# POVRotor.net
KiCad netlist of a schematic drawn in EAGLE
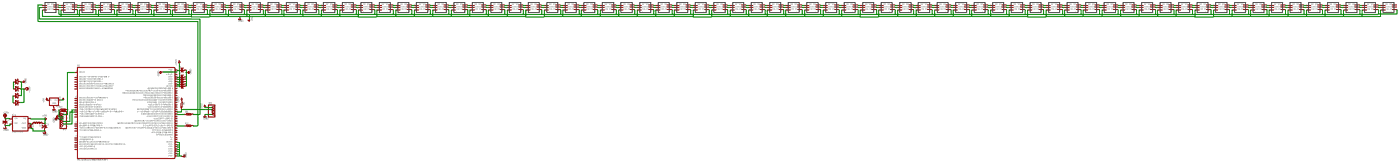
[diagram p0: schematic, sheet 1, overview]
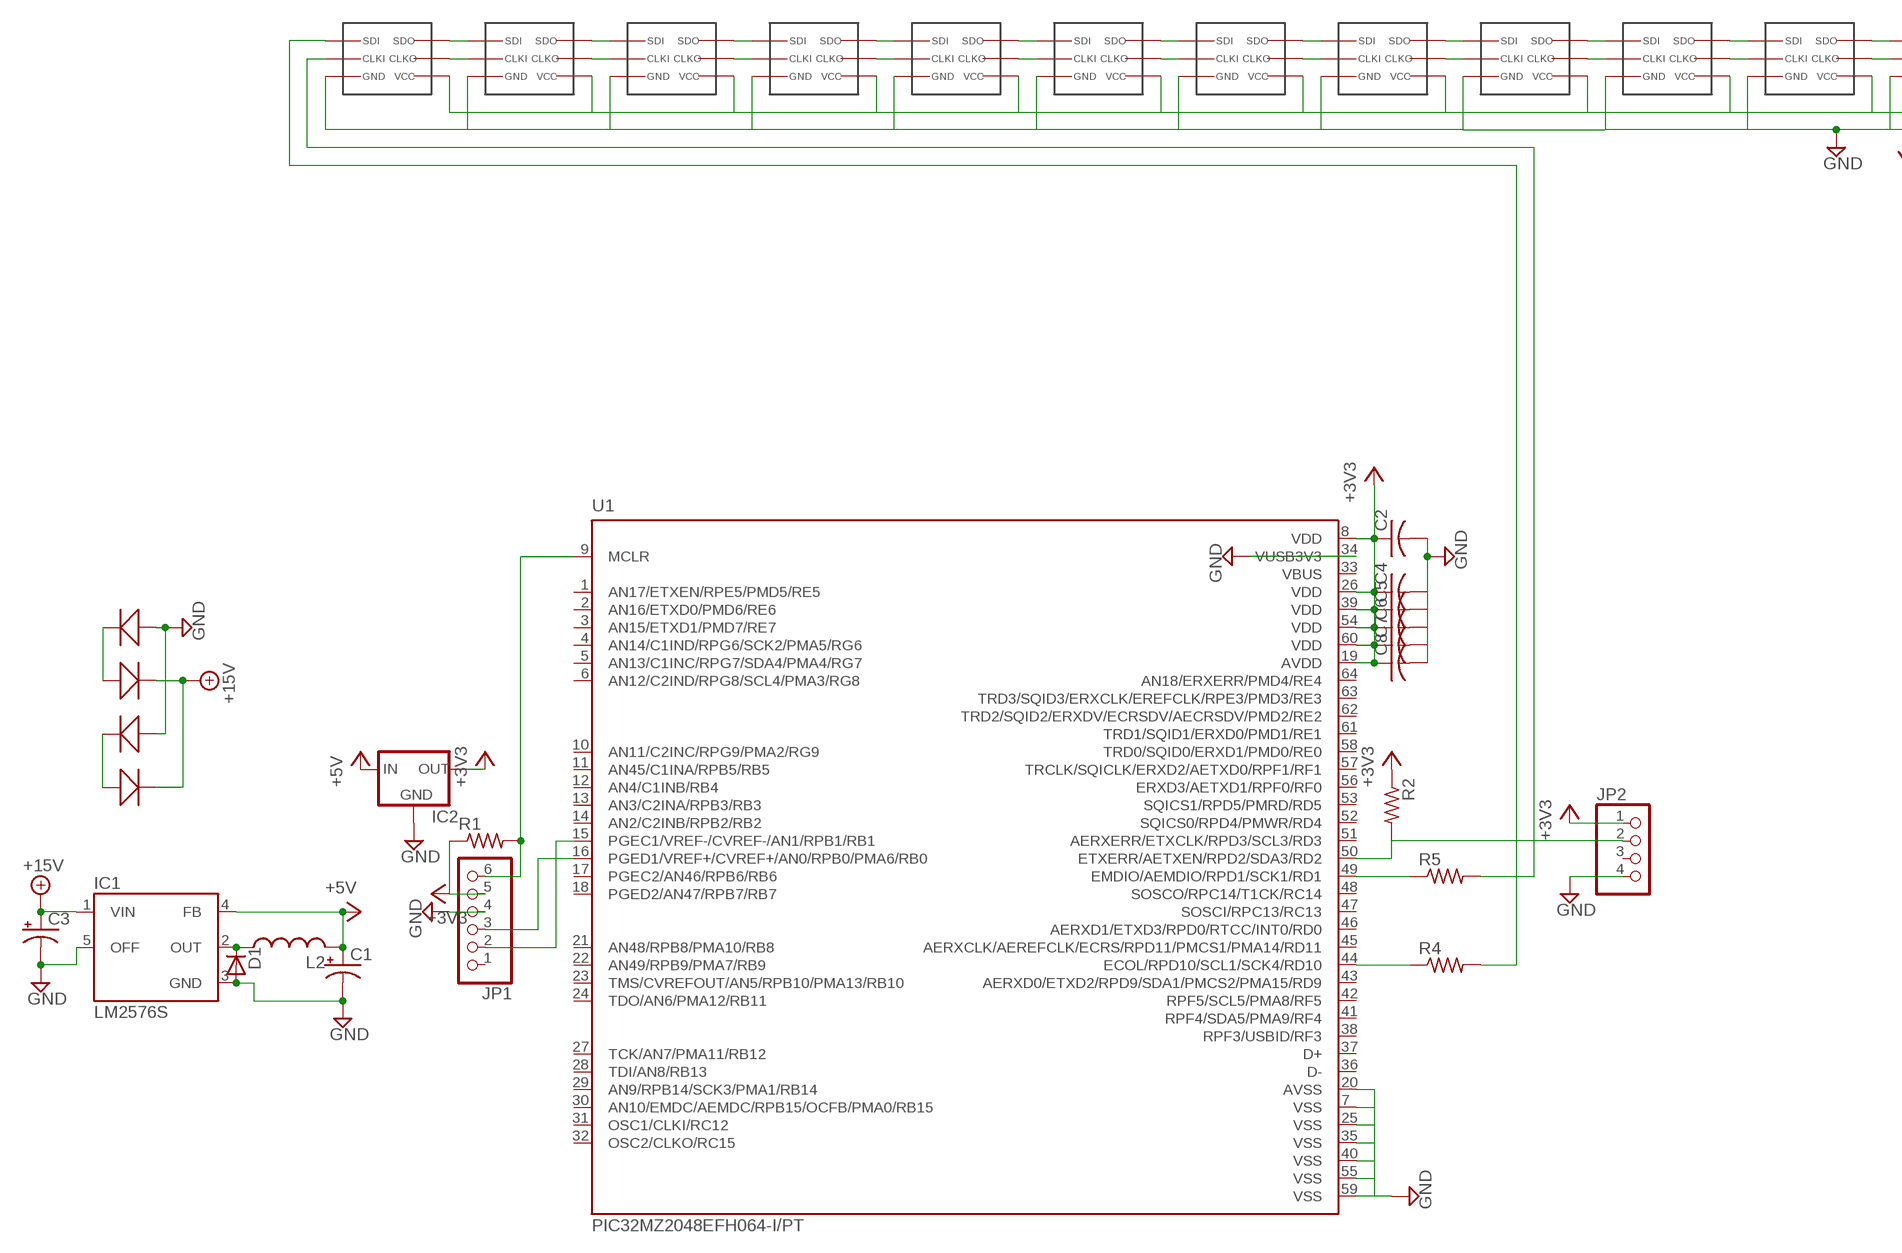
[diagram p1: schematic, sheet 1, part 1 of 8]
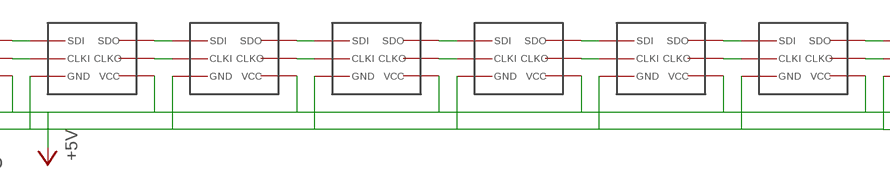
[diagram p2: schematic, sheet 1, part 2 of 8]
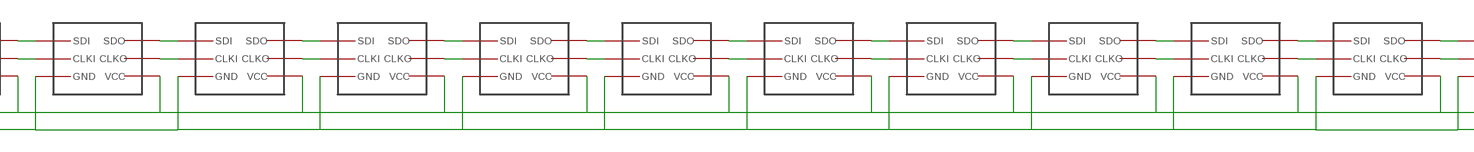
[diagram p3: schematic, sheet 1, part 3 of 8]
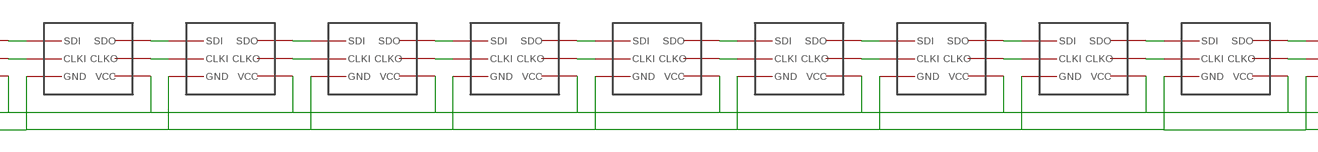
[diagram p4: schematic, sheet 1, part 4 of 8]
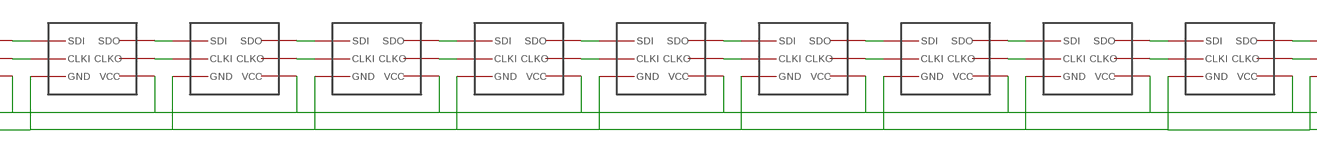
[diagram p5: schematic, sheet 1, part 5 of 8]
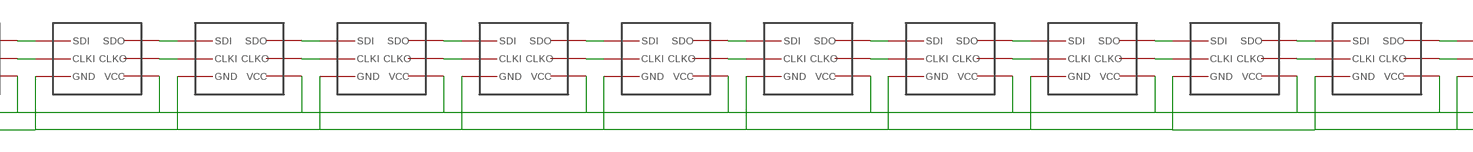
[diagram p6: schematic, sheet 1, part 6 of 8]
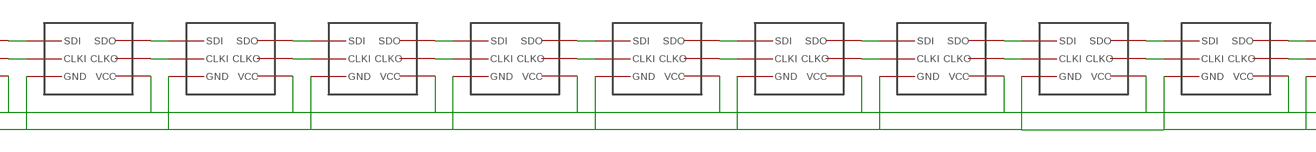
[diagram p7: schematic, sheet 1, part 7 of 8]
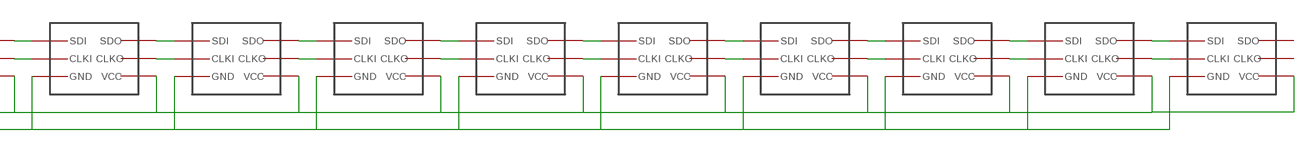
[diagram p8: schematic, sheet 1, part 8 of 8]

(export (version "E")
  (design (tool "Eeschema 10.0.6"))
  (components
    (comp (ref "C1")
      (value "CPOL-USE2,5-6E")
      (footprint "eagle-import:E2,5-6E")
      (libsource (lib "eagle-import") (part "CPOL-USE2,5-6E"))
    )
    (comp (ref "C2")
      (value "C-USC0805")
      (footprint "eagle-import:C0805")
      (libsource (lib "eagle-import") (part "C-USC0805"))
    )
    (comp (ref "C3")
      (value "CPOL-USE2,5-6E")
      (footprint "eagle-import:E2,5-6E")
      (libsource (lib "eagle-import") (part "CPOL-USE2,5-6E"))
    )
    (comp (ref "C4")
      (value "C-USC0805")
      (footprint "eagle-import:C0805")
      (libsource (lib "eagle-import") (part "C-USC0805"))
    )
    (comp (ref "C5")
      (value "C-USC0805")
      (footprint "eagle-import:C0805")
      (libsource (lib "eagle-import") (part "C-USC0805"))
    )
    (comp (ref "C6")
      (value "C-USC0805")
      (footprint "eagle-import:C0805")
      (libsource (lib "eagle-import") (part "C-USC0805"))
    )
    (comp (ref "C7")
      (value "C-USC0805")
      (footprint "eagle-import:C0805")
      (libsource (lib "eagle-import") (part "C-USC0805"))
    )
    (comp (ref "C8")
      (value "C-USC0805")
      (footprint "eagle-import:C0805")
      (libsource (lib "eagle-import") (part "C-USC0805"))
    )
    (comp (ref "D1")
      (value "BYS10")
      (footprint "eagle-import:SOD106A")
      (fields (field (name "MPN") "BYS10/45"))
      (libsource (lib "eagle-import") (part "BYS10"))
    )
    (comp (ref "D2")
      (value "SMD-DIODE-SCHOTTKY-40V-3A(DO-214AB)")
      (footprint "eagle-import:DO-214AB")
      (fields (field (name "MF") "Vishay") (field (name "MP") "SS34-E3/57T"))
      (libsource (lib "eagle-import") (part "SMD-DIODE-SCHOTTKY-40V-3A(DO-214AB)"))
    )
    (comp (ref "D3")
      (value "SMD-DIODE-SCHOTTKY-40V-3A(DO-214AB)")
      (footprint "eagle-import:DO-214AB")
      (fields (field (name "MF") "Vishay") (field (name "MP") "SS34-E3/57T"))
      (libsource (lib "eagle-import") (part "SMD-DIODE-SCHOTTKY-40V-3A(DO-214AB)"))
    )
    (comp (ref "D4")
      (value "SMD-DIODE-SCHOTTKY-40V-3A(DO-214AB)")
      (footprint "eagle-import:DO-214AB")
      (fields (field (name "MF") "Vishay") (field (name "MP") "SS34-E3/57T"))
      (libsource (lib "eagle-import") (part "SMD-DIODE-SCHOTTKY-40V-3A(DO-214AB)"))
    )
    (comp (ref "D5")
      (value "SMD-DIODE-SCHOTTKY-40V-3A(DO-214AB)")
      (footprint "eagle-import:DO-214AB")
      (fields (field (name "MF") "Vishay") (field (name "MP") "SS34-E3/57T"))
      (libsource (lib "eagle-import") (part "SMD-DIODE-SCHOTTKY-40V-3A(DO-214AB)"))
    )
    (comp (ref "IC1")
      (value "LM2576S")
      (footprint "eagle-import:TO263-5")
      (libsource (lib "eagle-import") (part "LM2576S"))
    )
    (comp (ref "IC2")
      (value "LM1117")
      (footprint "eagle-import:SOT223")
      (libsource (lib "eagle-import") (part "LM1117"))
    )
    (comp (ref "JP1")
      (value "PINHD-1X6/90")
      (footprint "eagle-import:1X06_90")
      (libsource (lib "eagle-import") (part "PINHD-1X6/90"))
    )
    (comp (ref "JP2")
      (value "PINHD-1X4")
      (footprint "eagle-import:1X04")
      (libsource (lib "eagle-import") (part "PINHD-1X4"))
    )
    (comp (ref "L2")
      (value "L-USL4532P")
      (footprint "eagle-import:L4532P")
      (libsource (lib "eagle-import") (part "L-USL4532P"))
    )
    (comp (ref "R1")
      (value "R-US_R0805")
      (footprint "eagle-import:R0805")
      (libsource (lib "eagle-import") (part "R-US_R0805"))
    )
    (comp (ref "R2")
      (value "R-US_R0603")
      (footprint "eagle-import:R0603")
      (libsource (lib "eagle-import") (part "R-US_R0603"))
    )
    (comp (ref "R4")
      (value "R-US_R0603")
      (footprint "eagle-import:R0603")
      (libsource (lib "eagle-import") (part "R-US_R0603"))
    )
    (comp (ref "R5")
      (value "R-US_R0603")
      (footprint "eagle-import:R0603")
      (libsource (lib "eagle-import") (part "R-US_R0603"))
    )
    (comp (ref "U$1")
      (value "2020LED")
      (footprint "eagle-import:2020LED")
      (libsource (lib "eagle-import") (part "2020LED"))
    )
    (comp (ref "U$2")
      (value "2020LED")
      (footprint "eagle-import:2020LED")
      (libsource (lib "eagle-import") (part "2020LED"))
    )
    (comp (ref "U$3")
      (value "2020LED")
      (footprint "eagle-import:2020LED")
      (libsource (lib "eagle-import") (part "2020LED"))
    )
    (comp (ref "U$4")
      (value "2020LED")
      (footprint "eagle-import:2020LED")
      (libsource (lib "eagle-import") (part "2020LED"))
    )
    (comp (ref "U$5")
      (value "2020LED")
      (footprint "eagle-import:2020LED")
      (libsource (lib "eagle-import") (part "2020LED"))
    )
    (comp (ref "U$6")
      (value "2020LED")
      (footprint "eagle-import:2020LED")
      (libsource (lib "eagle-import") (part "2020LED"))
    )
    (comp (ref "U$7")
      (value "2020LED")
      (footprint "eagle-import:2020LED")
      (libsource (lib "eagle-import") (part "2020LED"))
    )
    (comp (ref "U$8")
      (value "2020LED")
      (footprint "eagle-import:2020LED")
      (libsource (lib "eagle-import") (part "2020LED"))
    )
    (comp (ref "U$9")
      (value "2020LED")
      (footprint "eagle-import:2020LED")
      (libsource (lib "eagle-import") (part "2020LED"))
    )
    (comp (ref "U$10")
      (value "2020LED")
      (footprint "eagle-import:2020LED")
      (libsource (lib "eagle-import") (part "2020LED"))
    )
    (comp (ref "U$11")
      (value "2020LED")
      (footprint "eagle-import:2020LED")
      (libsource (lib "eagle-import") (part "2020LED"))
    )
    (comp (ref "U$12")
      (value "2020LED")
      (footprint "eagle-import:2020LED")
      (libsource (lib "eagle-import") (part "2020LED"))
    )
    (comp (ref "U$13")
      (value "2020LED")
      (footprint "eagle-import:2020LED")
      (libsource (lib "eagle-import") (part "2020LED"))
    )
    (comp (ref "U$14")
      (value "2020LED")
      (footprint "eagle-import:2020LED")
      (libsource (lib "eagle-import") (part "2020LED"))
    )
    (comp (ref "U$15")
      (value "2020LED")
      (footprint "eagle-import:2020LED")
      (libsource (lib "eagle-import") (part "2020LED"))
    )
    (comp (ref "U$16")
      (value "2020LED")
      (footprint "eagle-import:2020LED")
      (libsource (lib "eagle-import") (part "2020LED"))
    )
    (comp (ref "U$17")
      (value "2020LED")
      (footprint "eagle-import:2020LED")
      (libsource (lib "eagle-import") (part "2020LED"))
    )
    (comp (ref "U$18")
      (value "2020LED")
      (footprint "eagle-import:2020LED")
      (libsource (lib "eagle-import") (part "2020LED"))
    )
    (comp (ref "U$19")
      (value "2020LED")
      (footprint "eagle-import:2020LED")
      (libsource (lib "eagle-import") (part "2020LED"))
    )
    (comp (ref "U$20")
      (value "2020LED")
      (footprint "eagle-import:2020LED")
      (libsource (lib "eagle-import") (part "2020LED"))
    )
    (comp (ref "U$21")
      (value "2020LED")
      (footprint "eagle-import:2020LED")
      (libsource (lib "eagle-import") (part "2020LED"))
    )
    (comp (ref "U$22")
      (value "2020LED")
      (footprint "eagle-import:2020LED")
      (libsource (lib "eagle-import") (part "2020LED"))
    )
    (comp (ref "U$23")
      (value "2020LED")
      (footprint "eagle-import:2020LED")
      (libsource (lib "eagle-import") (part "2020LED"))
    )
    (comp (ref "U$24")
      (value "2020LED")
      (footprint "eagle-import:2020LED")
      (libsource (lib "eagle-import") (part "2020LED"))
    )
    (comp (ref "U$25")
      (value "2020LED")
      (footprint "eagle-import:2020LED")
      (libsource (lib "eagle-import") (part "2020LED"))
    )
    (comp (ref "U$26")
      (value "2020LED")
      (footprint "eagle-import:2020LED")
      (libsource (lib "eagle-import") (part "2020LED"))
    )
    (comp (ref "U$27")
      (value "2020LED")
      (footprint "eagle-import:2020LED")
      (libsource (lib "eagle-import") (part "2020LED"))
    )
    (comp (ref "U$28")
      (value "2020LED")
      (footprint "eagle-import:2020LED")
      (libsource (lib "eagle-import") (part "2020LED"))
    )
    (comp (ref "U$29")
      (value "2020LED")
      (footprint "eagle-import:2020LED")
      (libsource (lib "eagle-import") (part "2020LED"))
    )
    (comp (ref "U$30")
      (value "2020LED")
      (footprint "eagle-import:2020LED")
      (libsource (lib "eagle-import") (part "2020LED"))
    )
    (comp (ref "U$31")
      (value "2020LED")
      (footprint "eagle-import:2020LED")
      (libsource (lib "eagle-import") (part "2020LED"))
    )
    (comp (ref "U$32")
      (value "2020LED")
      (footprint "eagle-import:2020LED")
      (libsource (lib "eagle-import") (part "2020LED"))
    )
    (comp (ref "U$33")
      (value "2020LED")
      (footprint "eagle-import:2020LED")
      (libsource (lib "eagle-import") (part "2020LED"))
    )
    (comp (ref "U$34")
      (value "2020LED")
      (footprint "eagle-import:2020LED")
      (libsource (lib "eagle-import") (part "2020LED"))
    )
    (comp (ref "U$35")
      (value "2020LED")
      (footprint "eagle-import:2020LED")
      (libsource (lib "eagle-import") (part "2020LED"))
    )
    (comp (ref "U$36")
      (value "2020LED")
      (footprint "eagle-import:2020LED")
      (libsource (lib "eagle-import") (part "2020LED"))
    )
    (comp (ref "U$37")
      (value "2020LED")
      (footprint "eagle-import:2020LED")
      (libsource (lib "eagle-import") (part "2020LED"))
    )
    (comp (ref "U$38")
      (value "2020LED")
      (footprint "eagle-import:2020LED")
      (libsource (lib "eagle-import") (part "2020LED"))
    )
    (comp (ref "U$39")
      (value "2020LED")
      (footprint "eagle-import:2020LED")
      (libsource (lib "eagle-import") (part "2020LED"))
    )
    (comp (ref "U$40")
      (value "2020LED")
      (footprint "eagle-import:2020LED")
      (libsource (lib "eagle-import") (part "2020LED"))
    )
    (comp (ref "U$41")
      (value "2020LED")
      (footprint "eagle-import:2020LED")
      (libsource (lib "eagle-import") (part "2020LED"))
    )
    (comp (ref "U$42")
      (value "2020LED")
      (footprint "eagle-import:2020LED")
      (libsource (lib "eagle-import") (part "2020LED"))
    )
    (comp (ref "U$43")
      (value "2020LED")
      (footprint "eagle-import:2020LED")
      (libsource (lib "eagle-import") (part "2020LED"))
    )
    (comp (ref "U$44")
      (value "2020LED")
      (footprint "eagle-import:2020LED")
      (libsource (lib "eagle-import") (part "2020LED"))
    )
    (comp (ref "U$45")
      (value "2020LED")
      (footprint "eagle-import:2020LED")
      (libsource (lib "eagle-import") (part "2020LED"))
    )
    (comp (ref "U$46")
      (value "2020LED")
      (footprint "eagle-import:2020LED")
      (libsource (lib "eagle-import") (part "2020LED"))
    )
    (comp (ref "U$47")
      (value "2020LED")
      (footprint "eagle-import:2020LED")
      (libsource (lib "eagle-import") (part "2020LED"))
    )
    (comp (ref "U$48")
      (value "2020LED")
      (footprint "eagle-import:2020LED")
      (libsource (lib "eagle-import") (part "2020LED"))
    )
    (comp (ref "U$49")
      (value "2020LED")
      (footprint "eagle-import:2020LED")
      (libsource (lib "eagle-import") (part "2020LED"))
    )
    (comp (ref "U$50")
      (value "2020LED")
      (footprint "eagle-import:2020LED")
      (libsource (lib "eagle-import") (part "2020LED"))
    )
    (comp (ref "U$51")
      (value "2020LED")
      (footprint "eagle-import:2020LED")
      (libsource (lib "eagle-import") (part "2020LED"))
    )
    (comp (ref "U$52")
      (value "2020LED")
      (footprint "eagle-import:2020LED")
      (libsource (lib "eagle-import") (part "2020LED"))
    )
    (comp (ref "U$53")
      (value "2020LED")
      (footprint "eagle-import:2020LED")
      (libsource (lib "eagle-import") (part "2020LED"))
    )
    (comp (ref "U$54")
      (value "2020LED")
      (footprint "eagle-import:2020LED")
      (libsource (lib "eagle-import") (part "2020LED"))
    )
    (comp (ref "U$55")
      (value "2020LED")
      (footprint "eagle-import:2020LED")
      (libsource (lib "eagle-import") (part "2020LED"))
    )
    (comp (ref "U$56")
      (value "2020LED")
      (footprint "eagle-import:2020LED")
      (libsource (lib "eagle-import") (part "2020LED"))
    )
    (comp (ref "U$57")
      (value "2020LED")
      (footprint "eagle-import:2020LED")
      (libsource (lib "eagle-import") (part "2020LED"))
    )
    (comp (ref "U$58")
      (value "2020LED")
      (footprint "eagle-import:2020LED")
      (libsource (lib "eagle-import") (part "2020LED"))
    )
    (comp (ref "U$59")
      (value "2020LED")
      (footprint "eagle-import:2020LED")
      (libsource (lib "eagle-import") (part "2020LED"))
    )
    (comp (ref "U$60")
      (value "2020LED")
      (footprint "eagle-import:2020LED")
      (libsource (lib "eagle-import") (part "2020LED"))
    )
    (comp (ref "U$61")
      (value "2020LED")
      (footprint "eagle-import:2020LED")
      (libsource (lib "eagle-import") (part "2020LED"))
    )
    (comp (ref "U$62")
      (value "2020LED")
      (footprint "eagle-import:2020LED")
      (libsource (lib "eagle-import") (part "2020LED"))
    )
    (comp (ref "U$63")
      (value "2020LED")
      (footprint "eagle-import:2020LED")
      (libsource (lib "eagle-import") (part "2020LED"))
    )
    (comp (ref "U$64")
      (value "2020LED")
      (footprint "eagle-import:2020LED")
      (libsource (lib "eagle-import") (part "2020LED"))
    )
    (comp (ref "U$65")
      (value "2020LED")
      (footprint "eagle-import:2020LED")
      (libsource (lib "eagle-import") (part "2020LED"))
    )
    (comp (ref "U$66")
      (value "2020LED")
      (footprint "eagle-import:2020LED")
      (libsource (lib "eagle-import") (part "2020LED"))
    )
    (comp (ref "U$67")
      (value "2020LED")
      (footprint "eagle-import:2020LED")
      (libsource (lib "eagle-import") (part "2020LED"))
    )
    (comp (ref "U$68")
      (value "2020LED")
      (footprint "eagle-import:2020LED")
      (libsource (lib "eagle-import") (part "2020LED"))
    )
    (comp (ref "U$69")
      (value "2020LED")
      (footprint "eagle-import:2020LED")
      (libsource (lib "eagle-import") (part "2020LED"))
    )
    (comp (ref "U$70")
      (value "2020LED")
      (footprint "eagle-import:2020LED")
      (libsource (lib "eagle-import") (part "2020LED"))
    )
    (comp (ref "U$71")
      (value "2020LED")
      (footprint "eagle-import:2020LED")
      (libsource (lib "eagle-import") (part "2020LED"))
    )
    (comp (ref "U$72")
      (value "2020LED")
      (footprint "eagle-import:2020LED")
      (libsource (lib "eagle-import") (part "2020LED"))
    )
    (comp (ref "U$73")
      (value "2020LED")
      (footprint "eagle-import:2020LED")
      (libsource (lib "eagle-import") (part "2020LED"))
    )
    (comp (ref "U1")
      (value "PIC32MZ2048EFH064-I/PT")
      (footprint "eagle-import:QFP50P1200X1200X120-64N")
      (fields (field (name "MF") "Microchip"))
      (libsource (lib "eagle-import") (part "PIC32MZ2048EFH064-I/PT"))
    )
  )
  (nets
    (net (code "1") (name "+3V3") (class "Default")
      (node (ref "C2") (pin "1") (pinfunction "1_1") (pintype "passive"))
      (node (ref "C4") (pin "1") (pinfunction "1_1") (pintype "passive"))
      (node (ref "C5") (pin "1") (pinfunction "1_1") (pintype "passive"))
      (node (ref "C6") (pin "1") (pinfunction "1_1") (pintype "passive"))
      (node (ref "C7") (pin "1") (pinfunction "1_1") (pintype "passive"))
      (node (ref "C8") (pin "1") (pinfunction "1_1") (pintype "passive"))
      (node (ref "IC2") (pin "2") (pinfunction "OUT_2") (pintype "passive"))
      (node (ref "JP1") (pin "5") (pinfunction "5_5") (pintype "passive"))
      (node (ref "JP2") (pin "1") (pinfunction "1_1") (pintype "passive"))
      (node (ref "R1") (pin "1") (pinfunction "1_1") (pintype "passive"))
      (node (ref "R2") (pin "1") (pinfunction "1_1") (pintype "passive"))
      (node (ref "U1") (pin "19") (pinfunction "AVDD_19") (pintype "power_in"))
      (node (ref "U1") (pin "26") (pinfunction "VDD_26") (pintype "power_in"))
      (node (ref "U1") (pin "39") (pinfunction "VDD_39") (pintype "power_in"))
      (node (ref "U1") (pin "54") (pinfunction "VDD_54") (pintype "power_in"))
      (node (ref "U1") (pin "60") (pinfunction "VDD_60") (pintype "power_in"))
      (node (ref "U1") (pin "8") (pinfunction "VDD_8") (pintype "power_in"))
    )
    (net (code "2") (name "+5V") (class "Default")
      (node (ref "C1") (pin "+") (pinfunction "+_+") (pintype "passive"))
      (node (ref "IC1") (pin "4") (pinfunction "FB_4") (pintype "input"))
      (node (ref "IC2") (pin "3") (pinfunction "IN_3") (pintype "input"))
      (node (ref "L2") (pin "2") (pinfunction "2_2") (pintype "passive"))
      (node (ref "U$1") (pin "VCC") (pinfunction "VCC_VCC") (pintype "bidirectional"))
      (node (ref "U$10") (pin "VCC") (pinfunction "VCC_VCC") (pintype "bidirectional"))
      (node (ref "U$11") (pin "VCC") (pinfunction "VCC_VCC") (pintype "bidirectional"))
      (node (ref "U$12") (pin "VCC") (pinfunction "VCC_VCC") (pintype "bidirectional"))
      (node (ref "U$13") (pin "VCC") (pinfunction "VCC_VCC") (pintype "bidirectional"))
      (node (ref "U$14") (pin "VCC") (pinfunction "VCC_VCC") (pintype "bidirectional"))
      (node (ref "U$15") (pin "VCC") (pinfunction "VCC_VCC") (pintype "bidirectional"))
      (node (ref "U$16") (pin "VCC") (pinfunction "VCC_VCC") (pintype "bidirectional"))
      (node (ref "U$17") (pin "VCC") (pinfunction "VCC_VCC") (pintype "bidirectional"))
      (node (ref "U$18") (pin "VCC") (pinfunction "VCC_VCC") (pintype "bidirectional"))
      (node (ref "U$19") (pin "VCC") (pinfunction "VCC_VCC") (pintype "bidirectional"))
      (node (ref "U$2") (pin "VCC") (pinfunction "VCC_VCC") (pintype "bidirectional"))
      (node (ref "U$20") (pin "VCC") (pinfunction "VCC_VCC") (pintype "bidirectional"))
      (node (ref "U$21") (pin "VCC") (pinfunction "VCC_VCC") (pintype "bidirectional"))
      (node (ref "U$22") (pin "VCC") (pinfunction "VCC_VCC") (pintype "bidirectional"))
      (node (ref "U$23") (pin "VCC") (pinfunction "VCC_VCC") (pintype "bidirectional"))
      (node (ref "U$24") (pin "VCC") (pinfunction "VCC_VCC") (pintype "bidirectional"))
      (node (ref "U$25") (pin "VCC") (pinfunction "VCC_VCC") (pintype "bidirectional"))
      (node (ref "U$26") (pin "VCC") (pinfunction "VCC_VCC") (pintype "bidirectional"))
      (node (ref "U$27") (pin "VCC") (pinfunction "VCC_VCC") (pintype "bidirectional"))
      (node (ref "U$28") (pin "VCC") (pinfunction "VCC_VCC") (pintype "bidirectional"))
      (node (ref "U$29") (pin "VCC") (pinfunction "VCC_VCC") (pintype "bidirectional"))
      (node (ref "U$3") (pin "VCC") (pinfunction "VCC_VCC") (pintype "bidirectional"))
      (node (ref "U$30") (pin "VCC") (pinfunction "VCC_VCC") (pintype "bidirectional"))
      (node (ref "U$31") (pin "VCC") (pinfunction "VCC_VCC") (pintype "bidirectional"))
      (node (ref "U$32") (pin "VCC") (pinfunction "VCC_VCC") (pintype "bidirectional"))
      (node (ref "U$33") (pin "VCC") (pinfunction "VCC_VCC") (pintype "bidirectional"))
      (node (ref "U$34") (pin "VCC") (pinfunction "VCC_VCC") (pintype "bidirectional"))
      (node (ref "U$35") (pin "VCC") (pinfunction "VCC_VCC") (pintype "bidirectional"))
      (node (ref "U$36") (pin "VCC") (pinfunction "VCC_VCC") (pintype "bidirectional"))
      (node (ref "U$37") (pin "VCC") (pinfunction "VCC_VCC") (pintype "bidirectional"))
      (node (ref "U$38") (pin "VCC") (pinfunction "VCC_VCC") (pintype "bidirectional"))
      (node (ref "U$39") (pin "VCC") (pinfunction "VCC_VCC") (pintype "bidirectional"))
      (node (ref "U$4") (pin "VCC") (pinfunction "VCC_VCC") (pintype "bidirectional"))
      (node (ref "U$40") (pin "VCC") (pinfunction "VCC_VCC") (pintype "bidirectional"))
      (node (ref "U$41") (pin "VCC") (pinfunction "VCC_VCC") (pintype "bidirectional"))
      (node (ref "U$42") (pin "VCC") (pinfunction "VCC_VCC") (pintype "bidirectional"))
      (node (ref "U$43") (pin "VCC") (pinfunction "VCC_VCC") (pintype "bidirectional"))
      (node (ref "U$44") (pin "VCC") (pinfunction "VCC_VCC") (pintype "bidirectional"))
      (node (ref "U$45") (pin "VCC") (pinfunction "VCC_VCC") (pintype "bidirectional"))
      (node (ref "U$46") (pin "VCC") (pinfunction "VCC_VCC") (pintype "bidirectional"))
      (node (ref "U$47") (pin "VCC") (pinfunction "VCC_VCC") (pintype "bidirectional"))
      (node (ref "U$48") (pin "VCC") (pinfunction "VCC_VCC") (pintype "bidirectional"))
      (node (ref "U$49") (pin "VCC") (pinfunction "VCC_VCC") (pintype "bidirectional"))
      (node (ref "U$5") (pin "VCC") (pinfunction "VCC_VCC") (pintype "bidirectional"))
      (node (ref "U$50") (pin "VCC") (pinfunction "VCC_VCC") (pintype "bidirectional"))
      (node (ref "U$51") (pin "VCC") (pinfunction "VCC_VCC") (pintype "bidirectional"))
      (node (ref "U$52") (pin "VCC") (pinfunction "VCC_VCC") (pintype "bidirectional"))
      (node (ref "U$53") (pin "VCC") (pinfunction "VCC_VCC") (pintype "bidirectional"))
      (node (ref "U$54") (pin "VCC") (pinfunction "VCC_VCC") (pintype "bidirectional"))
      (node (ref "U$55") (pin "VCC") (pinfunction "VCC_VCC") (pintype "bidirectional"))
      (node (ref "U$56") (pin "VCC") (pinfunction "VCC_VCC") (pintype "bidirectional"))
      (node (ref "U$57") (pin "VCC") (pinfunction "VCC_VCC") (pintype "bidirectional"))
      (node (ref "U$58") (pin "VCC") (pinfunction "VCC_VCC") (pintype "bidirectional"))
      (node (ref "U$59") (pin "VCC") (pinfunction "VCC_VCC") (pintype "bidirectional"))
      (node (ref "U$6") (pin "VCC") (pinfunction "VCC_VCC") (pintype "bidirectional"))
      (node (ref "U$60") (pin "VCC") (pinfunction "VCC_VCC") (pintype "bidirectional"))
      (node (ref "U$61") (pin "VCC") (pinfunction "VCC_VCC") (pintype "bidirectional"))
      (node (ref "U$62") (pin "VCC") (pinfunction "VCC_VCC") (pintype "bidirectional"))
      (node (ref "U$63") (pin "VCC") (pinfunction "VCC_VCC") (pintype "bidirectional"))
      (node (ref "U$64") (pin "VCC") (pinfunction "VCC_VCC") (pintype "bidirectional"))
      (node (ref "U$65") (pin "VCC") (pinfunction "VCC_VCC") (pintype "bidirectional"))
      (node (ref "U$66") (pin "VCC") (pinfunction "VCC_VCC") (pintype "bidirectional"))
      (node (ref "U$67") (pin "VCC") (pinfunction "VCC_VCC") (pintype "bidirectional"))
      (node (ref "U$68") (pin "VCC") (pinfunction "VCC_VCC") (pintype "bidirectional"))
      (node (ref "U$69") (pin "VCC") (pinfunction "VCC_VCC") (pintype "bidirectional"))
      (node (ref "U$7") (pin "VCC") (pinfunction "VCC_VCC") (pintype "bidirectional"))
      (node (ref "U$70") (pin "VCC") (pinfunction "VCC_VCC") (pintype "bidirectional"))
      (node (ref "U$71") (pin "VCC") (pinfunction "VCC_VCC") (pintype "bidirectional"))
      (node (ref "U$72") (pin "VCC") (pinfunction "VCC_VCC") (pintype "bidirectional"))
      (node (ref "U$73") (pin "VCC") (pinfunction "VCC_VCC") (pintype "bidirectional"))
      (node (ref "U$8") (pin "VCC") (pinfunction "VCC_VCC") (pintype "bidirectional"))
      (node (ref "U$9") (pin "VCC") (pinfunction "VCC_VCC") (pintype "bidirectional"))
    )
    (net (code "3") (name "+15V") (class "Default")
      (node (ref "C3") (pin "+") (pinfunction "+_+") (pintype "passive"))
      (node (ref "D2") (pin "2") (pinfunction "-_2") (pintype "passive"))
      (node (ref "D3") (pin "2") (pinfunction "-_2") (pintype "passive"))
      (node (ref "IC1") (pin "1") (pinfunction "VIN_1") (pintype "power_in"))
    )
    (net (code "4") (name "/VBUS") (class "Default")
      (node (ref "U1") (pin "33") (pinfunction "VBUS_33") (pintype "power_in"))
    )
    (net (code "5") (name "GND") (class "Default")
      (node (ref "C1") (pin "-") (pinfunction "-_-") (pintype "passive"))
      (node (ref "C2") (pin "2") (pinfunction "2_2") (pintype "passive"))
      (node (ref "C3") (pin "-") (pinfunction "-_-") (pintype "passive"))
      (node (ref "C4") (pin "2") (pinfunction "2_2") (pintype "passive"))
      (node (ref "C5") (pin "2") (pinfunction "2_2") (pintype "passive"))
      (node (ref "C6") (pin "2") (pinfunction "2_2") (pintype "passive"))
      (node (ref "C7") (pin "2") (pinfunction "2_2") (pintype "passive"))
      (node (ref "C8") (pin "2") (pinfunction "2_2") (pintype "passive"))
      (node (ref "D1") (pin "A") (pinfunction "A_A") (pintype "passive"))
      (node (ref "D4") (pin "1") (pinfunction "+_1") (pintype "passive"))
      (node (ref "D5") (pin "1") (pinfunction "+_1") (pintype "passive"))
      (node (ref "IC1") (pin "3") (pinfunction "GND_3") (pintype "power_in"))
      (node (ref "IC1") (pin "5") (pinfunction "OFF_5") (pintype "input"))
      (node (ref "IC2") (pin "1") (pinfunction "GND_1") (pintype "input"))
      (node (ref "JP1") (pin "4") (pinfunction "4_4") (pintype "passive"))
      (node (ref "JP2") (pin "4") (pinfunction "4_4") (pintype "passive"))
      (node (ref "U$1") (pin "GND") (pinfunction "GND_GND") (pintype "bidirectional"))
      (node (ref "U$10") (pin "GND") (pinfunction "GND_GND") (pintype "bidirectional"))
      (node (ref "U$11") (pin "GND") (pinfunction "GND_GND") (pintype "bidirectional"))
      (node (ref "U$12") (pin "GND") (pinfunction "GND_GND") (pintype "bidirectional"))
      (node (ref "U$13") (pin "GND") (pinfunction "GND_GND") (pintype "bidirectional"))
      (node (ref "U$14") (pin "GND") (pinfunction "GND_GND") (pintype "bidirectional"))
      (node (ref "U$15") (pin "GND") (pinfunction "GND_GND") (pintype "bidirectional"))
      (node (ref "U$16") (pin "GND") (pinfunction "GND_GND") (pintype "bidirectional"))
      (node (ref "U$17") (pin "GND") (pinfunction "GND_GND") (pintype "bidirectional"))
      (node (ref "U$18") (pin "GND") (pinfunction "GND_GND") (pintype "bidirectional"))
      (node (ref "U$19") (pin "GND") (pinfunction "GND_GND") (pintype "bidirectional"))
      (node (ref "U$2") (pin "GND") (pinfunction "GND_GND") (pintype "bidirectional"))
      (node (ref "U$20") (pin "GND") (pinfunction "GND_GND") (pintype "bidirectional"))
      (node (ref "U$21") (pin "GND") (pinfunction "GND_GND") (pintype "bidirectional"))
      (node (ref "U$22") (pin "GND") (pinfunction "GND_GND") (pintype "bidirectional"))
      (node (ref "U$23") (pin "GND") (pinfunction "GND_GND") (pintype "bidirectional"))
      (node (ref "U$24") (pin "GND") (pinfunction "GND_GND") (pintype "bidirectional"))
      (node (ref "U$25") (pin "GND") (pinfunction "GND_GND") (pintype "bidirectional"))
      (node (ref "U$26") (pin "GND") (pinfunction "GND_GND") (pintype "bidirectional"))
      (node (ref "U$27") (pin "GND") (pinfunction "GND_GND") (pintype "bidirectional"))
      (node (ref "U$28") (pin "GND") (pinfunction "GND_GND") (pintype "bidirectional"))
      (node (ref "U$29") (pin "GND") (pinfunction "GND_GND") (pintype "bidirectional"))
      (node (ref "U$3") (pin "GND") (pinfunction "GND_GND") (pintype "bidirectional"))
      (node (ref "U$30") (pin "GND") (pinfunction "GND_GND") (pintype "bidirectional"))
      (node (ref "U$31") (pin "GND") (pinfunction "GND_GND") (pintype "bidirectional"))
      (node (ref "U$32") (pin "GND") (pinfunction "GND_GND") (pintype "bidirectional"))
      (node (ref "U$33") (pin "GND") (pinfunction "GND_GND") (pintype "bidirectional"))
      (node (ref "U$34") (pin "GND") (pinfunction "GND_GND") (pintype "bidirectional"))
      (node (ref "U$35") (pin "GND") (pinfunction "GND_GND") (pintype "bidirectional"))
      (node (ref "U$36") (pin "GND") (pinfunction "GND_GND") (pintype "bidirectional"))
      (node (ref "U$37") (pin "GND") (pinfunction "GND_GND") (pintype "bidirectional"))
      (node (ref "U$38") (pin "GND") (pinfunction "GND_GND") (pintype "bidirectional"))
      (node (ref "U$39") (pin "GND") (pinfunction "GND_GND") (pintype "bidirectional"))
      (node (ref "U$4") (pin "GND") (pinfunction "GND_GND") (pintype "bidirectional"))
      (node (ref "U$40") (pin "GND") (pinfunction "GND_GND") (pintype "bidirectional"))
      (node (ref "U$41") (pin "GND") (pinfunction "GND_GND") (pintype "bidirectional"))
      (node (ref "U$42") (pin "GND") (pinfunction "GND_GND") (pintype "bidirectional"))
      (node (ref "U$43") (pin "GND") (pinfunction "GND_GND") (pintype "bidirectional"))
      (node (ref "U$44") (pin "GND") (pinfunction "GND_GND") (pintype "bidirectional"))
      (node (ref "U$45") (pin "GND") (pinfunction "GND_GND") (pintype "bidirectional"))
      (node (ref "U$46") (pin "GND") (pinfunction "GND_GND") (pintype "bidirectional"))
      (node (ref "U$47") (pin "GND") (pinfunction "GND_GND") (pintype "bidirectional"))
      (node (ref "U$48") (pin "GND") (pinfunction "GND_GND") (pintype "bidirectional"))
      (node (ref "U$49") (pin "GND") (pinfunction "GND_GND") (pintype "bidirectional"))
      (node (ref "U$5") (pin "GND") (pinfunction "GND_GND") (pintype "bidirectional"))
      (node (ref "U$50") (pin "GND") (pinfunction "GND_GND") (pintype "bidirectional"))
      (node (ref "U$51") (pin "GND") (pinfunction "GND_GND") (pintype "bidirectional"))
      (node (ref "U$52") (pin "GND") (pinfunction "GND_GND") (pintype "bidirectional"))
      (node (ref "U$53") (pin "GND") (pinfunction "GND_GND") (pintype "bidirectional"))
      (node (ref "U$54") (pin "GND") (pinfunction "GND_GND") (pintype "bidirectional"))
      (node (ref "U$55") (pin "GND") (pinfunction "GND_GND") (pintype "bidirectional"))
      (node (ref "U$56") (pin "GND") (pinfunction "GND_GND") (pintype "bidirectional"))
      (node (ref "U$57") (pin "GND") (pinfunction "GND_GND") (pintype "bidirectional"))
      (node (ref "U$58") (pin "GND") (pinfunction "GND_GND") (pintype "bidirectional"))
      (node (ref "U$59") (pin "GND") (pinfunction "GND_GND") (pintype "bidirectional"))
      (node (ref "U$6") (pin "GND") (pinfunction "GND_GND") (pintype "bidirectional"))
      (node (ref "U$60") (pin "GND") (pinfunction "GND_GND") (pintype "bidirectional"))
      (node (ref "U$61") (pin "GND") (pinfunction "GND_GND") (pintype "bidirectional"))
      (node (ref "U$62") (pin "GND") (pinfunction "GND_GND") (pintype "bidirectional"))
      (node (ref "U$63") (pin "GND") (pinfunction "GND_GND") (pintype "bidirectional"))
      (node (ref "U$64") (pin "GND") (pinfunction "GND_GND") (pintype "bidirectional"))
      (node (ref "U$65") (pin "GND") (pinfunction "GND_GND") (pintype "bidirectional"))
      (node (ref "U$66") (pin "GND") (pinfunction "GND_GND") (pintype "bidirectional"))
      (node (ref "U$67") (pin "GND") (pinfunction "GND_GND") (pintype "bidirectional"))
      (node (ref "U$68") (pin "GND") (pinfunction "GND_GND") (pintype "bidirectional"))
      (node (ref "U$69") (pin "GND") (pinfunction "GND_GND") (pintype "bidirectional"))
      (node (ref "U$7") (pin "GND") (pinfunction "GND_GND") (pintype "bidirectional"))
      (node (ref "U$70") (pin "GND") (pinfunction "GND_GND") (pintype "bidirectional"))
      (node (ref "U$71") (pin "GND") (pinfunction "GND_GND") (pintype "bidirectional"))
      (node (ref "U$72") (pin "GND") (pinfunction "GND_GND") (pintype "bidirectional"))
      (node (ref "U$73") (pin "GND") (pinfunction "GND_GND") (pintype "bidirectional"))
      (node (ref "U$8") (pin "GND") (pinfunction "GND_GND") (pintype "bidirectional"))
      (node (ref "U$9") (pin "GND") (pinfunction "GND_GND") (pintype "bidirectional"))
      (node (ref "U1") (pin "20") (pinfunction "AVSS_20") (pintype "power_in"))
      (node (ref "U1") (pin "25") (pinfunction "VSS_25") (pintype "power_in"))
      (node (ref "U1") (pin "34") (pinfunction "VUSB3V3_34") (pintype "power_in"))
      (node (ref "U1") (pin "35") (pinfunction "VSS_35") (pintype "power_in"))
      (node (ref "U1") (pin "40") (pinfunction "VSS_40") (pintype "power_in"))
      (node (ref "U1") (pin "55") (pinfunction "VSS_55") (pintype "power_in"))
      (node (ref "U1") (pin "59") (pinfunction "VSS_59") (pintype "power_in"))
      (node (ref "U1") (pin "7") (pinfunction "VSS_7") (pintype "power_in"))
    )
    (net (code "6") (name "Net-(D2-+)") (class "Default")
      (node (ref "D2") (pin "1") (pinfunction "+_1") (pintype "passive"))
      (node (ref "D5") (pin "2") (pinfunction "-_2") (pintype "passive"))
    )
    (net (code "7") (name "Net-(D3-+)") (class "Default")
      (node (ref "D3") (pin "1") (pinfunction "+_1") (pintype "passive"))
      (node (ref "D4") (pin "2") (pinfunction "-_2") (pintype "passive"))
    )
    (net (code "8") (name "Net-(IC1-OUT)") (class "Default")
      (node (ref "D1") (pin "K") (pinfunction "K_K") (pintype "passive"))
      (node (ref "IC1") (pin "2") (pinfunction "OUT_2") (pintype "output"))
      (node (ref "L2") (pin "1") (pinfunction "1_1") (pintype "passive"))
    )
    (net (code "9") (name "Net-(R4-Pad2)") (class "Default")
      (node (ref "R4") (pin "2") (pinfunction "2_2") (pintype "passive"))
      (node (ref "U$2") (pin "SDI") (pinfunction "SDI_SDI") (pintype "bidirectional"))
    )
    (net (code "10") (name "Net-(R5-Pad2)") (class "Default")
      (node (ref "R5") (pin "2") (pinfunction "2_2") (pintype "passive"))
      (node (ref "U$2") (pin "CLKI") (pinfunction "CLKI_CLKI") (pintype "bidirectional"))
    )
    (net (code "11") (name "Net-(U$1-PadCLKI)") (class "Default")
      (node (ref "U$1") (pin "CLKI") (pinfunction "CLKI_CLKI") (pintype "bidirectional"))
      (node (ref "U$2") (pin "CLKO") (pinfunction "CLKO_CLKO") (pintype "bidirectional"))
    )
    (net (code "12") (name "Net-(U$1-PadCLKO)") (class "Default")
      (node (ref "U$1") (pin "CLKO") (pinfunction "CLKO_CLKO") (pintype "bidirectional"))
      (node (ref "U$3") (pin "CLKI") (pinfunction "CLKI_CLKI") (pintype "bidirectional"))
    )
    (net (code "13") (name "Net-(U$1-PadSDI)") (class "Default")
      (node (ref "U$1") (pin "SDI") (pinfunction "SDI_SDI") (pintype "bidirectional"))
      (node (ref "U$2") (pin "SDO") (pinfunction "SDO_SDO") (pintype "bidirectional"))
    )
    (net (code "14") (name "Net-(U$1-PadSDO)") (class "Default")
      (node (ref "U$1") (pin "SDO") (pinfunction "SDO_SDO") (pintype "bidirectional"))
      (node (ref "U$3") (pin "SDI") (pinfunction "SDI_SDI") (pintype "bidirectional"))
    )
    (net (code "15") (name "Net-(U$3-PadCLKO)") (class "Default")
      (node (ref "U$3") (pin "CLKO") (pinfunction "CLKO_CLKO") (pintype "bidirectional"))
      (node (ref "U$4") (pin "CLKI") (pinfunction "CLKI_CLKI") (pintype "bidirectional"))
    )
    (net (code "16") (name "Net-(U$3-PadSDO)") (class "Default")
      (node (ref "U$3") (pin "SDO") (pinfunction "SDO_SDO") (pintype "bidirectional"))
      (node (ref "U$4") (pin "SDI") (pinfunction "SDI_SDI") (pintype "bidirectional"))
    )
    (net (code "17") (name "Net-(U$4-PadCLKO)") (class "Default")
      (node (ref "U$4") (pin "CLKO") (pinfunction "CLKO_CLKO") (pintype "bidirectional"))
      (node (ref "U$5") (pin "CLKI") (pinfunction "CLKI_CLKI") (pintype "bidirectional"))
    )
    (net (code "18") (name "Net-(U$4-PadSDO)") (class "Default")
      (node (ref "U$4") (pin "SDO") (pinfunction "SDO_SDO") (pintype "bidirectional"))
      (node (ref "U$5") (pin "SDI") (pinfunction "SDI_SDI") (pintype "bidirectional"))
    )
    (net (code "19") (name "Net-(U$5-PadCLKO)") (class "Default")
      (node (ref "U$5") (pin "CLKO") (pinfunction "CLKO_CLKO") (pintype "bidirectional"))
      (node (ref "U$6") (pin "CLKI") (pinfunction "CLKI_CLKI") (pintype "bidirectional"))
    )
    (net (code "20") (name "Net-(U$5-PadSDO)") (class "Default")
      (node (ref "U$5") (pin "SDO") (pinfunction "SDO_SDO") (pintype "bidirectional"))
      (node (ref "U$6") (pin "SDI") (pinfunction "SDI_SDI") (pintype "bidirectional"))
    )
    (net (code "21") (name "Net-(U$6-PadCLKO)") (class "Default")
      (node (ref "U$6") (pin "CLKO") (pinfunction "CLKO_CLKO") (pintype "bidirectional"))
      (node (ref "U$7") (pin "CLKI") (pinfunction "CLKI_CLKI") (pintype "bidirectional"))
    )
    (net (code "22") (name "Net-(U$6-PadSDO)") (class "Default")
      (node (ref "U$6") (pin "SDO") (pinfunction "SDO_SDO") (pintype "bidirectional"))
      (node (ref "U$7") (pin "SDI") (pinfunction "SDI_SDI") (pintype "bidirectional"))
    )
    (net (code "23") (name "Net-(U$7-PadCLKO)") (class "Default")
      (node (ref "U$7") (pin "CLKO") (pinfunction "CLKO_CLKO") (pintype "bidirectional"))
      (node (ref "U$8") (pin "CLKI") (pinfunction "CLKI_CLKI") (pintype "bidirectional"))
    )
    (net (code "24") (name "Net-(U$7-PadSDO)") (class "Default")
      (node (ref "U$7") (pin "SDO") (pinfunction "SDO_SDO") (pintype "bidirectional"))
      (node (ref "U$8") (pin "SDI") (pinfunction "SDI_SDI") (pintype "bidirectional"))
    )
    (net (code "25") (name "Net-(U$8-PadCLKO)") (class "Default")
      (node (ref "U$8") (pin "CLKO") (pinfunction "CLKO_CLKO") (pintype "bidirectional"))
      (node (ref "U$9") (pin "CLKI") (pinfunction "CLKI_CLKI") (pintype "bidirectional"))
    )
    (net (code "26") (name "Net-(U$8-PadSDO)") (class "Default")
      (node (ref "U$8") (pin "SDO") (pinfunction "SDO_SDO") (pintype "bidirectional"))
      (node (ref "U$9") (pin "SDI") (pinfunction "SDI_SDI") (pintype "bidirectional"))
    )
    (net (code "27") (name "Net-(U$10-PadCLKI)") (class "Default")
      (node (ref "U$10") (pin "CLKI") (pinfunction "CLKI_CLKI") (pintype "bidirectional"))
      (node (ref "U$9") (pin "CLKO") (pinfunction "CLKO_CLKO") (pintype "bidirectional"))
    )
    (net (code "28") (name "Net-(U$10-PadCLKO)") (class "Default")
      (node (ref "U$10") (pin "CLKO") (pinfunction "CLKO_CLKO") (pintype "bidirectional"))
      (node (ref "U$11") (pin "CLKI") (pinfunction "CLKI_CLKI") (pintype "bidirectional"))
    )
    (net (code "29") (name "Net-(U$10-PadSDI)") (class "Default")
      (node (ref "U$10") (pin "SDI") (pinfunction "SDI_SDI") (pintype "bidirectional"))
      (node (ref "U$9") (pin "SDO") (pinfunction "SDO_SDO") (pintype "bidirectional"))
    )
    (net (code "30") (name "Net-(U$10-PadSDO)") (class "Default")
      (node (ref "U$10") (pin "SDO") (pinfunction "SDO_SDO") (pintype "bidirectional"))
      (node (ref "U$11") (pin "SDI") (pinfunction "SDI_SDI") (pintype "bidirectional"))
    )
    (net (code "31") (name "Net-(U$11-PadCLKO)") (class "Default")
      (node (ref "U$11") (pin "CLKO") (pinfunction "CLKO_CLKO") (pintype "bidirectional"))
      (node (ref "U$12") (pin "CLKI") (pinfunction "CLKI_CLKI") (pintype "bidirectional"))
    )
    (net (code "32") (name "Net-(U$11-PadSDO)") (class "Default")
      (node (ref "U$11") (pin "SDO") (pinfunction "SDO_SDO") (pintype "bidirectional"))
      (node (ref "U$12") (pin "SDI") (pinfunction "SDI_SDI") (pintype "bidirectional"))
    )
    (net (code "33") (name "Net-(U$12-PadCLKO)") (class "Default")
      (node (ref "U$12") (pin "CLKO") (pinfunction "CLKO_CLKO") (pintype "bidirectional"))
      (node (ref "U$13") (pin "CLKI") (pinfunction "CLKI_CLKI") (pintype "bidirectional"))
    )
    (net (code "34") (name "Net-(U$12-PadSDO)") (class "Default")
      (node (ref "U$12") (pin "SDO") (pinfunction "SDO_SDO") (pintype "bidirectional"))
      (node (ref "U$13") (pin "SDI") (pinfunction "SDI_SDI") (pintype "bidirectional"))
    )
    (net (code "35") (name "Net-(U$13-PadCLKO)") (class "Default")
      (node (ref "U$13") (pin "CLKO") (pinfunction "CLKO_CLKO") (pintype "bidirectional"))
      (node (ref "U$14") (pin "CLKI") (pinfunction "CLKI_CLKI") (pintype "bidirectional"))
    )
    (net (code "36") (name "Net-(U$13-PadSDO)") (class "Default")
      (node (ref "U$13") (pin "SDO") (pinfunction "SDO_SDO") (pintype "bidirectional"))
      (node (ref "U$14") (pin "SDI") (pinfunction "SDI_SDI") (pintype "bidirectional"))
    )
    (net (code "37") (name "Net-(U$14-PadCLKO)") (class "Default")
      (node (ref "U$14") (pin "CLKO") (pinfunction "CLKO_CLKO") (pintype "bidirectional"))
      (node (ref "U$15") (pin "CLKI") (pinfunction "CLKI_CLKI") (pintype "bidirectional"))
    )
    (net (code "38") (name "Net-(U$14-PadSDO)") (class "Default")
      (node (ref "U$14") (pin "SDO") (pinfunction "SDO_SDO") (pintype "bidirectional"))
      (node (ref "U$15") (pin "SDI") (pinfunction "SDI_SDI") (pintype "bidirectional"))
    )
    (net (code "39") (name "Net-(U$15-PadCLKO)") (class "Default")
      (node (ref "U$15") (pin "CLKO") (pinfunction "CLKO_CLKO") (pintype "bidirectional"))
      (node (ref "U$16") (pin "CLKI") (pinfunction "CLKI_CLKI") (pintype "bidirectional"))
    )
    (net (code "40") (name "Net-(U$15-PadSDO)") (class "Default")
      (node (ref "U$15") (pin "SDO") (pinfunction "SDO_SDO") (pintype "bidirectional"))
      (node (ref "U$16") (pin "SDI") (pinfunction "SDI_SDI") (pintype "bidirectional"))
    )
    (net (code "41") (name "Net-(U$16-PadCLKO)") (class "Default")
      (node (ref "U$16") (pin "CLKO") (pinfunction "CLKO_CLKO") (pintype "bidirectional"))
      (node (ref "U$17") (pin "CLKI") (pinfunction "CLKI_CLKI") (pintype "bidirectional"))
    )
    (net (code "42") (name "Net-(U$16-PadSDO)") (class "Default")
      (node (ref "U$16") (pin "SDO") (pinfunction "SDO_SDO") (pintype "bidirectional"))
      (node (ref "U$17") (pin "SDI") (pinfunction "SDI_SDI") (pintype "bidirectional"))
    )
    (net (code "43") (name "Net-(U$17-PadCLKO)") (class "Default")
      (node (ref "U$17") (pin "CLKO") (pinfunction "CLKO_CLKO") (pintype "bidirectional"))
      (node (ref "U$18") (pin "CLKI") (pinfunction "CLKI_CLKI") (pintype "bidirectional"))
    )
    (net (code "44") (name "Net-(U$17-PadSDO)") (class "Default")
      (node (ref "U$17") (pin "SDO") (pinfunction "SDO_SDO") (pintype "bidirectional"))
      (node (ref "U$18") (pin "SDI") (pinfunction "SDI_SDI") (pintype "bidirectional"))
    )
    (net (code "45") (name "Net-(U$18-PadCLKO)") (class "Default")
      (node (ref "U$18") (pin "CLKO") (pinfunction "CLKO_CLKO") (pintype "bidirectional"))
      (node (ref "U$19") (pin "CLKI") (pinfunction "CLKI_CLKI") (pintype "bidirectional"))
    )
    (net (code "46") (name "Net-(U$18-PadSDO)") (class "Default")
      (node (ref "U$18") (pin "SDO") (pinfunction "SDO_SDO") (pintype "bidirectional"))
      (node (ref "U$19") (pin "SDI") (pinfunction "SDI_SDI") (pintype "bidirectional"))
    )
    (net (code "47") (name "Net-(U$19-PadCLKO)") (class "Default")
      (node (ref "U$19") (pin "CLKO") (pinfunction "CLKO_CLKO") (pintype "bidirectional"))
      (node (ref "U$20") (pin "CLKI") (pinfunction "CLKI_CLKI") (pintype "bidirectional"))
    )
    (net (code "48") (name "Net-(U$19-PadSDO)") (class "Default")
      (node (ref "U$19") (pin "SDO") (pinfunction "SDO_SDO") (pintype "bidirectional"))
      (node (ref "U$20") (pin "SDI") (pinfunction "SDI_SDI") (pintype "bidirectional"))
    )
    (net (code "49") (name "Net-(U$20-PadCLKO)") (class "Default")
      (node (ref "U$20") (pin "CLKO") (pinfunction "CLKO_CLKO") (pintype "bidirectional"))
      (node (ref "U$21") (pin "CLKI") (pinfunction "CLKI_CLKI") (pintype "bidirectional"))
    )
    (net (code "50") (name "Net-(U$20-PadSDO)") (class "Default")
      (node (ref "U$20") (pin "SDO") (pinfunction "SDO_SDO") (pintype "bidirectional"))
      (node (ref "U$21") (pin "SDI") (pinfunction "SDI_SDI") (pintype "bidirectional"))
    )
    (net (code "51") (name "Net-(U$21-PadCLKO)") (class "Default")
      (node (ref "U$21") (pin "CLKO") (pinfunction "CLKO_CLKO") (pintype "bidirectional"))
      (node (ref "U$22") (pin "CLKI") (pinfunction "CLKI_CLKI") (pintype "bidirectional"))
    )
    (net (code "52") (name "Net-(U$21-PadSDO)") (class "Default")
      (node (ref "U$21") (pin "SDO") (pinfunction "SDO_SDO") (pintype "bidirectional"))
      (node (ref "U$22") (pin "SDI") (pinfunction "SDI_SDI") (pintype "bidirectional"))
    )
    (net (code "53") (name "Net-(U$22-PadCLKO)") (class "Default")
      (node (ref "U$22") (pin "CLKO") (pinfunction "CLKO_CLKO") (pintype "bidirectional"))
      (node (ref "U$23") (pin "CLKI") (pinfunction "CLKI_CLKI") (pintype "bidirectional"))
    )
    (net (code "54") (name "Net-(U$22-PadSDO)") (class "Default")
      (node (ref "U$22") (pin "SDO") (pinfunction "SDO_SDO") (pintype "bidirectional"))
      (node (ref "U$23") (pin "SDI") (pinfunction "SDI_SDI") (pintype "bidirectional"))
    )
    (net (code "55") (name "Net-(U$23-PadCLKO)") (class "Default")
      (node (ref "U$23") (pin "CLKO") (pinfunction "CLKO_CLKO") (pintype "bidirectional"))
      (node (ref "U$24") (pin "CLKI") (pinfunction "CLKI_CLKI") (pintype "bidirectional"))
    )
    (net (code "56") (name "Net-(U$23-PadSDO)") (class "Default")
      (node (ref "U$23") (pin "SDO") (pinfunction "SDO_SDO") (pintype "bidirectional"))
      (node (ref "U$24") (pin "SDI") (pinfunction "SDI_SDI") (pintype "bidirectional"))
    )
    (net (code "57") (name "Net-(U$24-PadCLKO)") (class "Default")
      (node (ref "U$24") (pin "CLKO") (pinfunction "CLKO_CLKO") (pintype "bidirectional"))
      (node (ref "U$25") (pin "CLKI") (pinfunction "CLKI_CLKI") (pintype "bidirectional"))
    )
    (net (code "58") (name "Net-(U$24-PadSDO)") (class "Default")
      (node (ref "U$24") (pin "SDO") (pinfunction "SDO_SDO") (pintype "bidirectional"))
      (node (ref "U$25") (pin "SDI") (pinfunction "SDI_SDI") (pintype "bidirectional"))
    )
    (net (code "59") (name "Net-(U$25-PadCLKO)") (class "Default")
      (node (ref "U$25") (pin "CLKO") (pinfunction "CLKO_CLKO") (pintype "bidirectional"))
      (node (ref "U$26") (pin "CLKI") (pinfunction "CLKI_CLKI") (pintype "bidirectional"))
    )
    (net (code "60") (name "Net-(U$25-PadSDO)") (class "Default")
      (node (ref "U$25") (pin "SDO") (pinfunction "SDO_SDO") (pintype "bidirectional"))
      (node (ref "U$26") (pin "SDI") (pinfunction "SDI_SDI") (pintype "bidirectional"))
    )
    (net (code "61") (name "Net-(U$26-PadCLKO)") (class "Default")
      (node (ref "U$26") (pin "CLKO") (pinfunction "CLKO_CLKO") (pintype "bidirectional"))
      (node (ref "U$27") (pin "CLKI") (pinfunction "CLKI_CLKI") (pintype "bidirectional"))
    )
    (net (code "62") (name "Net-(U$26-PadSDO)") (class "Default")
      (node (ref "U$26") (pin "SDO") (pinfunction "SDO_SDO") (pintype "bidirectional"))
      (node (ref "U$27") (pin "SDI") (pinfunction "SDI_SDI") (pintype "bidirectional"))
    )
    (net (code "63") (name "Net-(U$27-PadCLKO)") (class "Default")
      (node (ref "U$27") (pin "CLKO") (pinfunction "CLKO_CLKO") (pintype "bidirectional"))
      (node (ref "U$28") (pin "CLKI") (pinfunction "CLKI_CLKI") (pintype "bidirectional"))
    )
    (net (code "64") (name "Net-(U$27-PadSDO)") (class "Default")
      (node (ref "U$27") (pin "SDO") (pinfunction "SDO_SDO") (pintype "bidirectional"))
      (node (ref "U$28") (pin "SDI") (pinfunction "SDI_SDI") (pintype "bidirectional"))
    )
    (net (code "65") (name "Net-(U$28-PadCLKO)") (class "Default")
      (node (ref "U$28") (pin "CLKO") (pinfunction "CLKO_CLKO") (pintype "bidirectional"))
      (node (ref "U$29") (pin "CLKI") (pinfunction "CLKI_CLKI") (pintype "bidirectional"))
    )
    (net (code "66") (name "Net-(U$28-PadSDO)") (class "Default")
      (node (ref "U$28") (pin "SDO") (pinfunction "SDO_SDO") (pintype "bidirectional"))
      (node (ref "U$29") (pin "SDI") (pinfunction "SDI_SDI") (pintype "bidirectional"))
    )
    (net (code "67") (name "Net-(U$29-PadCLKO)") (class "Default")
      (node (ref "U$29") (pin "CLKO") (pinfunction "CLKO_CLKO") (pintype "bidirectional"))
      (node (ref "U$30") (pin "CLKI") (pinfunction "CLKI_CLKI") (pintype "bidirectional"))
    )
    (net (code "68") (name "Net-(U$29-PadSDO)") (class "Default")
      (node (ref "U$29") (pin "SDO") (pinfunction "SDO_SDO") (pintype "bidirectional"))
      (node (ref "U$30") (pin "SDI") (pinfunction "SDI_SDI") (pintype "bidirectional"))
    )
    (net (code "69") (name "Net-(U$30-PadCLKO)") (class "Default")
      (node (ref "U$30") (pin "CLKO") (pinfunction "CLKO_CLKO") (pintype "bidirectional"))
      (node (ref "U$31") (pin "CLKI") (pinfunction "CLKI_CLKI") (pintype "bidirectional"))
    )
    (net (code "70") (name "Net-(U$30-PadSDO)") (class "Default")
      (node (ref "U$30") (pin "SDO") (pinfunction "SDO_SDO") (pintype "bidirectional"))
      (node (ref "U$31") (pin "SDI") (pinfunction "SDI_SDI") (pintype "bidirectional"))
    )
    (net (code "71") (name "Net-(U$31-PadCLKO)") (class "Default")
      (node (ref "U$31") (pin "CLKO") (pinfunction "CLKO_CLKO") (pintype "bidirectional"))
      (node (ref "U$32") (pin "CLKI") (pinfunction "CLKI_CLKI") (pintype "bidirectional"))
    )
    (net (code "72") (name "Net-(U$31-PadSDO)") (class "Default")
      (node (ref "U$31") (pin "SDO") (pinfunction "SDO_SDO") (pintype "bidirectional"))
      (node (ref "U$32") (pin "SDI") (pinfunction "SDI_SDI") (pintype "bidirectional"))
    )
    (net (code "73") (name "Net-(U$32-PadCLKO)") (class "Default")
      (node (ref "U$32") (pin "CLKO") (pinfunction "CLKO_CLKO") (pintype "bidirectional"))
      (node (ref "U$33") (pin "CLKI") (pinfunction "CLKI_CLKI") (pintype "bidirectional"))
    )
    (net (code "74") (name "Net-(U$32-PadSDO)") (class "Default")
      (node (ref "U$32") (pin "SDO") (pinfunction "SDO_SDO") (pintype "bidirectional"))
      (node (ref "U$33") (pin "SDI") (pinfunction "SDI_SDI") (pintype "bidirectional"))
    )
    (net (code "75") (name "Net-(U$33-PadCLKO)") (class "Default")
      (node (ref "U$33") (pin "CLKO") (pinfunction "CLKO_CLKO") (pintype "bidirectional"))
      (node (ref "U$34") (pin "CLKI") (pinfunction "CLKI_CLKI") (pintype "bidirectional"))
    )
    (net (code "76") (name "Net-(U$33-PadSDO)") (class "Default")
      (node (ref "U$33") (pin "SDO") (pinfunction "SDO_SDO") (pintype "bidirectional"))
      (node (ref "U$34") (pin "SDI") (pinfunction "SDI_SDI") (pintype "bidirectional"))
    )
    (net (code "77") (name "Net-(U$34-PadCLKO)") (class "Default")
      (node (ref "U$34") (pin "CLKO") (pinfunction "CLKO_CLKO") (pintype "bidirectional"))
      (node (ref "U$35") (pin "CLKI") (pinfunction "CLKI_CLKI") (pintype "bidirectional"))
    )
    (net (code "78") (name "Net-(U$34-PadSDO)") (class "Default")
      (node (ref "U$34") (pin "SDO") (pinfunction "SDO_SDO") (pintype "bidirectional"))
      (node (ref "U$35") (pin "SDI") (pinfunction "SDI_SDI") (pintype "bidirectional"))
    )
    (net (code "79") (name "Net-(U$35-PadCLKO)") (class "Default")
      (node (ref "U$35") (pin "CLKO") (pinfunction "CLKO_CLKO") (pintype "bidirectional"))
      (node (ref "U$36") (pin "CLKI") (pinfunction "CLKI_CLKI") (pintype "bidirectional"))
    )
    (net (code "80") (name "Net-(U$35-PadSDO)") (class "Default")
      (node (ref "U$35") (pin "SDO") (pinfunction "SDO_SDO") (pintype "bidirectional"))
      (node (ref "U$36") (pin "SDI") (pinfunction "SDI_SDI") (pintype "bidirectional"))
    )
    (net (code "81") (name "Net-(U$36-PadCLKO)") (class "Default")
      (node (ref "U$36") (pin "CLKO") (pinfunction "CLKO_CLKO") (pintype "bidirectional"))
      (node (ref "U$37") (pin "CLKI") (pinfunction "CLKI_CLKI") (pintype "bidirectional"))
    )
    (net (code "82") (name "Net-(U$36-PadSDO)") (class "Default")
      (node (ref "U$36") (pin "SDO") (pinfunction "SDO_SDO") (pintype "bidirectional"))
      (node (ref "U$37") (pin "SDI") (pinfunction "SDI_SDI") (pintype "bidirectional"))
    )
    (net (code "83") (name "Net-(U$37-PadCLKO)") (class "Default")
      (node (ref "U$37") (pin "CLKO") (pinfunction "CLKO_CLKO") (pintype "bidirectional"))
      (node (ref "U$38") (pin "CLKI") (pinfunction "CLKI_CLKI") (pintype "bidirectional"))
    )
    (net (code "84") (name "Net-(U$37-PadSDO)") (class "Default")
      (node (ref "U$37") (pin "SDO") (pinfunction "SDO_SDO") (pintype "bidirectional"))
      (node (ref "U$38") (pin "SDI") (pinfunction "SDI_SDI") (pintype "bidirectional"))
    )
    (net (code "85") (name "Net-(U$38-PadCLKO)") (class "Default")
      (node (ref "U$38") (pin "CLKO") (pinfunction "CLKO_CLKO") (pintype "bidirectional"))
      (node (ref "U$39") (pin "CLKI") (pinfunction "CLKI_CLKI") (pintype "bidirectional"))
    )
    (net (code "86") (name "Net-(U$38-PadSDO)") (class "Default")
      (node (ref "U$38") (pin "SDO") (pinfunction "SDO_SDO") (pintype "bidirectional"))
      (node (ref "U$39") (pin "SDI") (pinfunction "SDI_SDI") (pintype "bidirectional"))
    )
    (net (code "87") (name "Net-(U$39-PadCLKO)") (class "Default")
      (node (ref "U$39") (pin "CLKO") (pinfunction "CLKO_CLKO") (pintype "bidirectional"))
      (node (ref "U$40") (pin "CLKI") (pinfunction "CLKI_CLKI") (pintype "bidirectional"))
    )
    (net (code "88") (name "Net-(U$39-PadSDO)") (class "Default")
      (node (ref "U$39") (pin "SDO") (pinfunction "SDO_SDO") (pintype "bidirectional"))
      (node (ref "U$40") (pin "SDI") (pinfunction "SDI_SDI") (pintype "bidirectional"))
    )
    (net (code "89") (name "Net-(U$40-PadCLKO)") (class "Default")
      (node (ref "U$40") (pin "CLKO") (pinfunction "CLKO_CLKO") (pintype "bidirectional"))
      (node (ref "U$41") (pin "CLKI") (pinfunction "CLKI_CLKI") (pintype "bidirectional"))
    )
    (net (code "90") (name "Net-(U$40-PadSDO)") (class "Default")
      (node (ref "U$40") (pin "SDO") (pinfunction "SDO_SDO") (pintype "bidirectional"))
      (node (ref "U$41") (pin "SDI") (pinfunction "SDI_SDI") (pintype "bidirectional"))
    )
    (net (code "91") (name "Net-(U$41-PadCLKO)") (class "Default")
      (node (ref "U$41") (pin "CLKO") (pinfunction "CLKO_CLKO") (pintype "bidirectional"))
      (node (ref "U$42") (pin "CLKI") (pinfunction "CLKI_CLKI") (pintype "bidirectional"))
    )
    (net (code "92") (name "Net-(U$41-PadSDO)") (class "Default")
      (node (ref "U$41") (pin "SDO") (pinfunction "SDO_SDO") (pintype "bidirectional"))
      (node (ref "U$42") (pin "SDI") (pinfunction "SDI_SDI") (pintype "bidirectional"))
    )
    (net (code "93") (name "Net-(U$42-PadCLKO)") (class "Default")
      (node (ref "U$42") (pin "CLKO") (pinfunction "CLKO_CLKO") (pintype "bidirectional"))
      (node (ref "U$43") (pin "CLKI") (pinfunction "CLKI_CLKI") (pintype "bidirectional"))
    )
    (net (code "94") (name "Net-(U$42-PadSDO)") (class "Default")
      (node (ref "U$42") (pin "SDO") (pinfunction "SDO_SDO") (pintype "bidirectional"))
      (node (ref "U$43") (pin "SDI") (pinfunction "SDI_SDI") (pintype "bidirectional"))
    )
    (net (code "95") (name "Net-(U$43-PadCLKO)") (class "Default")
      (node (ref "U$43") (pin "CLKO") (pinfunction "CLKO_CLKO") (pintype "bidirectional"))
      (node (ref "U$44") (pin "CLKI") (pinfunction "CLKI_CLKI") (pintype "bidirectional"))
    )
    (net (code "96") (name "Net-(U$43-PadSDO)") (class "Default")
      (node (ref "U$43") (pin "SDO") (pinfunction "SDO_SDO") (pintype "bidirectional"))
      (node (ref "U$44") (pin "SDI") (pinfunction "SDI_SDI") (pintype "bidirectional"))
    )
    (net (code "97") (name "Net-(U$44-PadCLKO)") (class "Default")
      (node (ref "U$44") (pin "CLKO") (pinfunction "CLKO_CLKO") (pintype "bidirectional"))
      (node (ref "U$45") (pin "CLKI") (pinfunction "CLKI_CLKI") (pintype "bidirectional"))
    )
    (net (code "98") (name "Net-(U$44-PadSDO)") (class "Default")
      (node (ref "U$44") (pin "SDO") (pinfunction "SDO_SDO") (pintype "bidirectional"))
      (node (ref "U$45") (pin "SDI") (pinfunction "SDI_SDI") (pintype "bidirectional"))
    )
    (net (code "99") (name "Net-(U$45-PadCLKO)") (class "Default")
      (node (ref "U$45") (pin "CLKO") (pinfunction "CLKO_CLKO") (pintype "bidirectional"))
      (node (ref "U$46") (pin "CLKI") (pinfunction "CLKI_CLKI") (pintype "bidirectional"))
    )
    (net (code "100") (name "Net-(U$45-PadSDO)") (class "Default")
      (node (ref "U$45") (pin "SDO") (pinfunction "SDO_SDO") (pintype "bidirectional"))
      (node (ref "U$46") (pin "SDI") (pinfunction "SDI_SDI") (pintype "bidirectional"))
    )
    (net (code "101") (name "Net-(U$46-PadCLKO)") (class "Default")
      (node (ref "U$46") (pin "CLKO") (pinfunction "CLKO_CLKO") (pintype "bidirectional"))
      (node (ref "U$47") (pin "CLKI") (pinfunction "CLKI_CLKI") (pintype "bidirectional"))
    )
    (net (code "102") (name "Net-(U$46-PadSDO)") (class "Default")
      (node (ref "U$46") (pin "SDO") (pinfunction "SDO_SDO") (pintype "bidirectional"))
      (node (ref "U$47") (pin "SDI") (pinfunction "SDI_SDI") (pintype "bidirectional"))
    )
    (net (code "103") (name "Net-(U$47-PadCLKO)") (class "Default")
      (node (ref "U$47") (pin "CLKO") (pinfunction "CLKO_CLKO") (pintype "bidirectional"))
      (node (ref "U$48") (pin "CLKI") (pinfunction "CLKI_CLKI") (pintype "bidirectional"))
    )
    (net (code "104") (name "Net-(U$47-PadSDO)") (class "Default")
      (node (ref "U$47") (pin "SDO") (pinfunction "SDO_SDO") (pintype "bidirectional"))
      (node (ref "U$48") (pin "SDI") (pinfunction "SDI_SDI") (pintype "bidirectional"))
    )
    (net (code "105") (name "Net-(U$48-PadCLKO)") (class "Default")
      (node (ref "U$48") (pin "CLKO") (pinfunction "CLKO_CLKO") (pintype "bidirectional"))
      (node (ref "U$49") (pin "CLKI") (pinfunction "CLKI_CLKI") (pintype "bidirectional"))
    )
    (net (code "106") (name "Net-(U$48-PadSDO)") (class "Default")
      (node (ref "U$48") (pin "SDO") (pinfunction "SDO_SDO") (pintype "bidirectional"))
      (node (ref "U$49") (pin "SDI") (pinfunction "SDI_SDI") (pintype "bidirectional"))
    )
    (net (code "107") (name "Net-(U$49-PadCLKO)") (class "Default")
      (node (ref "U$49") (pin "CLKO") (pinfunction "CLKO_CLKO") (pintype "bidirectional"))
      (node (ref "U$50") (pin "CLKI") (pinfunction "CLKI_CLKI") (pintype "bidirectional"))
    )
    (net (code "108") (name "Net-(U$49-PadSDO)") (class "Default")
      (node (ref "U$49") (pin "SDO") (pinfunction "SDO_SDO") (pintype "bidirectional"))
      (node (ref "U$50") (pin "SDI") (pinfunction "SDI_SDI") (pintype "bidirectional"))
    )
    (net (code "109") (name "Net-(U$50-PadCLKO)") (class "Default")
      (node (ref "U$50") (pin "CLKO") (pinfunction "CLKO_CLKO") (pintype "bidirectional"))
      (node (ref "U$51") (pin "CLKI") (pinfunction "CLKI_CLKI") (pintype "bidirectional"))
    )
    (net (code "110") (name "Net-(U$50-PadSDO)") (class "Default")
      (node (ref "U$50") (pin "SDO") (pinfunction "SDO_SDO") (pintype "bidirectional"))
      (node (ref "U$51") (pin "SDI") (pinfunction "SDI_SDI") (pintype "bidirectional"))
    )
    (net (code "111") (name "Net-(U$51-PadCLKO)") (class "Default")
      (node (ref "U$51") (pin "CLKO") (pinfunction "CLKO_CLKO") (pintype "bidirectional"))
      (node (ref "U$52") (pin "CLKI") (pinfunction "CLKI_CLKI") (pintype "bidirectional"))
    )
    (net (code "112") (name "Net-(U$51-PadSDO)") (class "Default")
      (node (ref "U$51") (pin "SDO") (pinfunction "SDO_SDO") (pintype "bidirectional"))
      (node (ref "U$52") (pin "SDI") (pinfunction "SDI_SDI") (pintype "bidirectional"))
    )
    (net (code "113") (name "Net-(U$52-PadCLKO)") (class "Default")
      (node (ref "U$52") (pin "CLKO") (pinfunction "CLKO_CLKO") (pintype "bidirectional"))
      (node (ref "U$53") (pin "CLKI") (pinfunction "CLKI_CLKI") (pintype "bidirectional"))
    )
    (net (code "114") (name "Net-(U$52-PadSDO)") (class "Default")
      (node (ref "U$52") (pin "SDO") (pinfunction "SDO_SDO") (pintype "bidirectional"))
      (node (ref "U$53") (pin "SDI") (pinfunction "SDI_SDI") (pintype "bidirectional"))
    )
    (net (code "115") (name "Net-(U$53-PadCLKO)") (class "Default")
      (node (ref "U$53") (pin "CLKO") (pinfunction "CLKO_CLKO") (pintype "bidirectional"))
      (node (ref "U$54") (pin "CLKI") (pinfunction "CLKI_CLKI") (pintype "bidirectional"))
    )
    (net (code "116") (name "Net-(U$53-PadSDO)") (class "Default")
      (node (ref "U$53") (pin "SDO") (pinfunction "SDO_SDO") (pintype "bidirectional"))
      (node (ref "U$54") (pin "SDI") (pinfunction "SDI_SDI") (pintype "bidirectional"))
    )
    (net (code "117") (name "Net-(U$54-PadCLKO)") (class "Default")
      (node (ref "U$54") (pin "CLKO") (pinfunction "CLKO_CLKO") (pintype "bidirectional"))
      (node (ref "U$55") (pin "CLKI") (pinfunction "CLKI_CLKI") (pintype "bidirectional"))
    )
    (net (code "118") (name "Net-(U$54-PadSDO)") (class "Default")
      (node (ref "U$54") (pin "SDO") (pinfunction "SDO_SDO") (pintype "bidirectional"))
      (node (ref "U$55") (pin "SDI") (pinfunction "SDI_SDI") (pintype "bidirectional"))
    )
    (net (code "119") (name "Net-(U$55-PadCLKO)") (class "Default")
      (node (ref "U$55") (pin "CLKO") (pinfunction "CLKO_CLKO") (pintype "bidirectional"))
      (node (ref "U$56") (pin "CLKI") (pinfunction "CLKI_CLKI") (pintype "bidirectional"))
    )
    (net (code "120") (name "Net-(U$55-PadSDO)") (class "Default")
      (node (ref "U$55") (pin "SDO") (pinfunction "SDO_SDO") (pintype "bidirectional"))
      (node (ref "U$56") (pin "SDI") (pinfunction "SDI_SDI") (pintype "bidirectional"))
    )
    (net (code "121") (name "Net-(U$56-PadCLKO)") (class "Default")
      (node (ref "U$56") (pin "CLKO") (pinfunction "CLKO_CLKO") (pintype "bidirectional"))
      (node (ref "U$57") (pin "CLKI") (pinfunction "CLKI_CLKI") (pintype "bidirectional"))
    )
    (net (code "122") (name "Net-(U$56-PadSDO)") (class "Default")
      (node (ref "U$56") (pin "SDO") (pinfunction "SDO_SDO") (pintype "bidirectional"))
      (node (ref "U$57") (pin "SDI") (pinfunction "SDI_SDI") (pintype "bidirectional"))
    )
    (net (code "123") (name "Net-(U$57-PadCLKO)") (class "Default")
      (node (ref "U$57") (pin "CLKO") (pinfunction "CLKO_CLKO") (pintype "bidirectional"))
      (node (ref "U$58") (pin "CLKI") (pinfunction "CLKI_CLKI") (pintype "bidirectional"))
    )
    (net (code "124") (name "Net-(U$57-PadSDO)") (class "Default")
      (node (ref "U$57") (pin "SDO") (pinfunction "SDO_SDO") (pintype "bidirectional"))
      (node (ref "U$58") (pin "SDI") (pinfunction "SDI_SDI") (pintype "bidirectional"))
    )
    (net (code "125") (name "Net-(U$58-PadCLKO)") (class "Default")
      (node (ref "U$58") (pin "CLKO") (pinfunction "CLKO_CLKO") (pintype "bidirectional"))
      (node (ref "U$59") (pin "CLKI") (pinfunction "CLKI_CLKI") (pintype "bidirectional"))
    )
    (net (code "126") (name "Net-(U$58-PadSDO)") (class "Default")
      (node (ref "U$58") (pin "SDO") (pinfunction "SDO_SDO") (pintype "bidirectional"))
      (node (ref "U$59") (pin "SDI") (pinfunction "SDI_SDI") (pintype "bidirectional"))
    )
    (net (code "127") (name "Net-(U$59-PadCLKO)") (class "Default")
      (node (ref "U$59") (pin "CLKO") (pinfunction "CLKO_CLKO") (pintype "bidirectional"))
      (node (ref "U$60") (pin "CLKI") (pinfunction "CLKI_CLKI") (pintype "bidirectional"))
    )
    (net (code "128") (name "Net-(U$59-PadSDO)") (class "Default")
      (node (ref "U$59") (pin "SDO") (pinfunction "SDO_SDO") (pintype "bidirectional"))
      (node (ref "U$60") (pin "SDI") (pinfunction "SDI_SDI") (pintype "bidirectional"))
    )
    (net (code "129") (name "Net-(U$60-PadCLKO)") (class "Default")
      (node (ref "U$60") (pin "CLKO") (pinfunction "CLKO_CLKO") (pintype "bidirectional"))
      (node (ref "U$61") (pin "CLKI") (pinfunction "CLKI_CLKI") (pintype "bidirectional"))
    )
    (net (code "130") (name "Net-(U$60-PadSDO)") (class "Default")
      (node (ref "U$60") (pin "SDO") (pinfunction "SDO_SDO") (pintype "bidirectional"))
      (node (ref "U$61") (pin "SDI") (pinfunction "SDI_SDI") (pintype "bidirectional"))
    )
    (net (code "131") (name "Net-(U$61-PadCLKO)") (class "Default")
      (node (ref "U$61") (pin "CLKO") (pinfunction "CLKO_CLKO") (pintype "bidirectional"))
      (node (ref "U$62") (pin "CLKI") (pinfunction "CLKI_CLKI") (pintype "bidirectional"))
    )
    (net (code "132") (name "Net-(U$61-PadSDO)") (class "Default")
      (node (ref "U$61") (pin "SDO") (pinfunction "SDO_SDO") (pintype "bidirectional"))
      (node (ref "U$62") (pin "SDI") (pinfunction "SDI_SDI") (pintype "bidirectional"))
    )
    (net (code "133") (name "Net-(U$62-PadCLKO)") (class "Default")
      (node (ref "U$62") (pin "CLKO") (pinfunction "CLKO_CLKO") (pintype "bidirectional"))
      (node (ref "U$63") (pin "CLKI") (pinfunction "CLKI_CLKI") (pintype "bidirectional"))
    )
    (net (code "134") (name "Net-(U$62-PadSDO)") (class "Default")
      (node (ref "U$62") (pin "SDO") (pinfunction "SDO_SDO") (pintype "bidirectional"))
      (node (ref "U$63") (pin "SDI") (pinfunction "SDI_SDI") (pintype "bidirectional"))
    )
    (net (code "135") (name "Net-(U$63-PadCLKO)") (class "Default")
      (node (ref "U$63") (pin "CLKO") (pinfunction "CLKO_CLKO") (pintype "bidirectional"))
      (node (ref "U$64") (pin "CLKI") (pinfunction "CLKI_CLKI") (pintype "bidirectional"))
    )
    (net (code "136") (name "Net-(U$63-PadSDO)") (class "Default")
      (node (ref "U$63") (pin "SDO") (pinfunction "SDO_SDO") (pintype "bidirectional"))
      (node (ref "U$64") (pin "SDI") (pinfunction "SDI_SDI") (pintype "bidirectional"))
    )
    (net (code "137") (name "Net-(U$64-PadCLKO)") (class "Default")
      (node (ref "U$64") (pin "CLKO") (pinfunction "CLKO_CLKO") (pintype "bidirectional"))
      (node (ref "U$65") (pin "CLKI") (pinfunction "CLKI_CLKI") (pintype "bidirectional"))
    )
    (net (code "138") (name "Net-(U$64-PadSDO)") (class "Default")
      (node (ref "U$64") (pin "SDO") (pinfunction "SDO_SDO") (pintype "bidirectional"))
      (node (ref "U$65") (pin "SDI") (pinfunction "SDI_SDI") (pintype "bidirectional"))
    )
    (net (code "139") (name "Net-(U$65-PadCLKO)") (class "Default")
      (node (ref "U$65") (pin "CLKO") (pinfunction "CLKO_CLKO") (pintype "bidirectional"))
      (node (ref "U$66") (pin "CLKI") (pinfunction "CLKI_CLKI") (pintype "bidirectional"))
    )
    (net (code "140") (name "Net-(U$65-PadSDO)") (class "Default")
      (node (ref "U$65") (pin "SDO") (pinfunction "SDO_SDO") (pintype "bidirectional"))
      (node (ref "U$66") (pin "SDI") (pinfunction "SDI_SDI") (pintype "bidirectional"))
    )
    (net (code "141") (name "Net-(U$66-PadCLKO)") (class "Default")
      (node (ref "U$66") (pin "CLKO") (pinfunction "CLKO_CLKO") (pintype "bidirectional"))
      (node (ref "U$67") (pin "CLKI") (pinfunction "CLKI_CLKI") (pintype "bidirectional"))
    )
    (net (code "142") (name "Net-(U$66-PadSDO)") (class "Default")
      (node (ref "U$66") (pin "SDO") (pinfunction "SDO_SDO") (pintype "bidirectional"))
      (node (ref "U$67") (pin "SDI") (pinfunction "SDI_SDI") (pintype "bidirectional"))
    )
    (net (code "143") (name "Net-(U$67-PadCLKO)") (class "Default")
      (node (ref "U$67") (pin "CLKO") (pinfunction "CLKO_CLKO") (pintype "bidirectional"))
      (node (ref "U$68") (pin "CLKI") (pinfunction "CLKI_CLKI") (pintype "bidirectional"))
    )
    (net (code "144") (name "Net-(U$67-PadSDO)") (class "Default")
      (node (ref "U$67") (pin "SDO") (pinfunction "SDO_SDO") (pintype "bidirectional"))
      (node (ref "U$68") (pin "SDI") (pinfunction "SDI_SDI") (pintype "bidirectional"))
    )
    (net (code "145") (name "Net-(U$68-PadCLKO)") (class "Default")
      (node (ref "U$68") (pin "CLKO") (pinfunction "CLKO_CLKO") (pintype "bidirectional"))
      (node (ref "U$69") (pin "CLKI") (pinfunction "CLKI_CLKI") (pintype "bidirectional"))
    )
    (net (code "146") (name "Net-(U$68-PadSDO)") (class "Default")
      (node (ref "U$68") (pin "SDO") (pinfunction "SDO_SDO") (pintype "bidirectional"))
      (node (ref "U$69") (pin "SDI") (pinfunction "SDI_SDI") (pintype "bidirectional"))
    )
    (net (code "147") (name "Net-(U$69-PadCLKO)") (class "Default")
      (node (ref "U$69") (pin "CLKO") (pinfunction "CLKO_CLKO") (pintype "bidirectional"))
      (node (ref "U$70") (pin "CLKI") (pinfunction "CLKI_CLKI") (pintype "bidirectional"))
    )
    (net (code "148") (name "Net-(U$69-PadSDO)") (class "Default")
      (node (ref "U$69") (pin "SDO") (pinfunction "SDO_SDO") (pintype "bidirectional"))
      (node (ref "U$70") (pin "SDI") (pinfunction "SDI_SDI") (pintype "bidirectional"))
    )
    (net (code "149") (name "Net-(U$70-PadCLKO)") (class "Default")
      (node (ref "U$70") (pin "CLKO") (pinfunction "CLKO_CLKO") (pintype "bidirectional"))
      (node (ref "U$71") (pin "CLKI") (pinfunction "CLKI_CLKI") (pintype "bidirectional"))
    )
    (net (code "150") (name "Net-(U$70-PadSDO)") (class "Default")
      (node (ref "U$70") (pin "SDO") (pinfunction "SDO_SDO") (pintype "bidirectional"))
      (node (ref "U$71") (pin "SDI") (pinfunction "SDI_SDI") (pintype "bidirectional"))
    )
    (net (code "151") (name "Net-(U$71-PadCLKO)") (class "Default")
      (node (ref "U$71") (pin "CLKO") (pinfunction "CLKO_CLKO") (pintype "bidirectional"))
      (node (ref "U$72") (pin "CLKI") (pinfunction "CLKI_CLKI") (pintype "bidirectional"))
    )
    (net (code "152") (name "Net-(U$71-PadSDO)") (class "Default")
      (node (ref "U$71") (pin "SDO") (pinfunction "SDO_SDO") (pintype "bidirectional"))
      (node (ref "U$72") (pin "SDI") (pinfunction "SDI_SDI") (pintype "bidirectional"))
    )
    (net (code "153") (name "Net-(U$72-PadCLKO)") (class "Default")
      (node (ref "U$72") (pin "CLKO") (pinfunction "CLKO_CLKO") (pintype "bidirectional"))
      (node (ref "U$73") (pin "CLKI") (pinfunction "CLKI_CLKI") (pintype "bidirectional"))
    )
    (net (code "154") (name "Net-(U$72-PadSDO)") (class "Default")
      (node (ref "U$72") (pin "SDO") (pinfunction "SDO_SDO") (pintype "bidirectional"))
      (node (ref "U$73") (pin "SDI") (pinfunction "SDI_SDI") (pintype "bidirectional"))
    )
    (net (code "155") (name "Net-(U1-ECOL{slash}RPD10{slash}SCL1{slash}SCK4{slash}RD10)") (class "Default")
      (node (ref "R4") (pin "1") (pinfunction "1_1") (pintype "passive"))
      (node (ref "U1") (pin "44") (pinfunction "ECOL/RPD10/SCL1/SCK4/RD10_44") (pintype "bidirectional"))
    )
    (net (code "156") (name "Net-(U1-EMDIO{slash}AEMDIO{slash}RPD1{slash}SCK1{slash}RD1)") (class "Default")
      (node (ref "R5") (pin "1") (pinfunction "1_1") (pintype "passive"))
      (node (ref "U1") (pin "49") (pinfunction "EMDIO/AEMDIO/RPD1/SCK1/RD1_49") (pintype "bidirectional"))
    )
    (net (code "157") (name "Net-(U1-ETXERR{slash}AETXEN{slash}RPD2{slash}SDA3{slash}RD2)") (class "Default")
      (node (ref "JP2") (pin "2") (pinfunction "2_2") (pintype "passive"))
      (node (ref "R2") (pin "2") (pinfunction "2_2") (pintype "passive"))
      (node (ref "U1") (pin "50") (pinfunction "ETXERR/AETXEN/RPD2/SDA3/RD2_50") (pintype "bidirectional"))
    )
    (net (code "158") (name "Net-(U1-MCLR)") (class "Default")
      (node (ref "JP1") (pin "6") (pinfunction "6_6") (pintype "passive"))
      (node (ref "R1") (pin "2") (pinfunction "2_2") (pintype "passive"))
      (node (ref "U1") (pin "9") (pinfunction "MCLR_9") (pintype "input"))
    )
    (net (code "159") (name "Net-(U1-PGEC1{slash}VREF-{slash}CVREF-{slash}AN1{slash}RPB1{slash}RB1)") (class "Default")
      (node (ref "JP1") (pin "2") (pinfunction "2_2") (pintype "passive"))
      (node (ref "U1") (pin "15") (pinfunction "PGEC1/VREF-/CVREF-/AN1/RPB1/RB1_15") (pintype "bidirectional"))
    )
    (net (code "160") (name "Net-(U1-PGED1{slash}VREF+{slash}CVREF+{slash}AN0{slash}RPB0{slash}PMA6{slash}RB0)") (class "Default")
      (node (ref "JP1") (pin "3") (pinfunction "3_3") (pintype "passive"))
      (node (ref "U1") (pin "16") (pinfunction "PGED1/VREF+/CVREF+/AN0/RPB0/PMA6/RB0_16") (pintype "bidirectional"))
    )
    (net (code "161") (name "unconnected-(JP1-Pad1)") (class "Default")
      (node (ref "JP1") (pin "1") (pinfunction "1_1") (pintype "passive"))
    )
    (net (code "162") (name "unconnected-(JP2-Pad3)") (class "Default")
      (node (ref "JP2") (pin "3") (pinfunction "3_3") (pintype "passive"))
    )
    (net (code "163") (name "unconnected-(U$73-PadCLKO)") (class "Default")
      (node (ref "U$73") (pin "CLKO") (pinfunction "CLKO_CLKO") (pintype "bidirectional"))
    )
    (net (code "164") (name "unconnected-(U$73-PadSDO)") (class "Default")
      (node (ref "U$73") (pin "SDO") (pinfunction "SDO_SDO") (pintype "bidirectional"))
    )
    (net (code "165") (name "unconnected-(U1-AERXCLK{slash}AEREFCLK{slash}ECRS{slash}RPD11{slash}PMCS1{slash}PMA14{slash}RD11-Pad45)") (class "Default")
      (node (ref "U1") (pin "45") (pinfunction "AERXCLK/AEREFCLK/ECRS/RPD11/PMCS1/PMA14/RD11_45") (pintype "bidirectional"))
    )
    (net (code "166") (name "unconnected-(U1-AERXD0{slash}ETXD2{slash}RPD9{slash}SDA1{slash}PMCS2{slash}PMA15{slash}RD9-Pad43)") (class "Default")
      (node (ref "U1") (pin "43") (pinfunction "AERXD0/ETXD2/RPD9/SDA1/PMCS2/PMA15/RD9_43") (pintype "bidirectional"))
    )
    (net (code "167") (name "unconnected-(U1-AERXD1{slash}ETXD3{slash}RPD0{slash}RTCC{slash}INT0{slash}RD0-Pad46)") (class "Default")
      (node (ref "U1") (pin "46") (pinfunction "AERXD1/ETXD3/RPD0/RTCC/INT0/RD0_46") (pintype "bidirectional"))
    )
    (net (code "168") (name "unconnected-(U1-AERXERR{slash}ETXCLK{slash}RPD3{slash}SCL3{slash}RD3-Pad51)") (class "Default")
      (node (ref "U1") (pin "51") (pinfunction "AERXERR/ETXCLK/RPD3/SCL3/RD3_51") (pintype "bidirectional"))
    )
    (net (code "169") (name "unconnected-(U1-AN2{slash}C2INB{slash}RPB2{slash}RB2-Pad14)") (class "Default")
      (node (ref "U1") (pin "14") (pinfunction "AN2/C2INB/RPB2/RB2_14") (pintype "bidirectional"))
    )
    (net (code "170") (name "unconnected-(U1-AN3{slash}C2INA{slash}RPB3{slash}RB3-Pad13)") (class "Default")
      (node (ref "U1") (pin "13") (pinfunction "AN3/C2INA/RPB3/RB3_13") (pintype "bidirectional"))
    )
    (net (code "171") (name "unconnected-(U1-AN4{slash}C1INB{slash}RB4-Pad12)") (class "Default")
      (node (ref "U1") (pin "12") (pinfunction "AN4/C1INB/RB4_12") (pintype "bidirectional"))
    )
    (net (code "172") (name "unconnected-(U1-AN9{slash}RPB14{slash}SCK3{slash}PMA1{slash}RB14-Pad29)") (class "Default")
      (node (ref "U1") (pin "29") (pinfunction "AN9/RPB14/SCK3/PMA1/RB14_29") (pintype "bidirectional"))
    )
    (net (code "173") (name "unconnected-(U1-AN10{slash}EMDC{slash}AEMDC{slash}RPB15{slash}OCFB{slash}PMA0{slash}RB15-Pad30)") (class "Default")
      (node (ref "U1") (pin "30") (pinfunction "AN10/EMDC/AEMDC/RPB15/OCFB/PMA0/RB15_30") (pintype "bidirectional"))
    )
    (net (code "174") (name "unconnected-(U1-AN11{slash}C2INC{slash}RPG9{slash}PMA2{slash}RG9-Pad10)") (class "Default")
      (node (ref "U1") (pin "10") (pinfunction "AN11/C2INC/RPG9/PMA2/RG9_10") (pintype "bidirectional"))
    )
    (net (code "175") (name "unconnected-(U1-AN12{slash}C2IND{slash}RPG8{slash}SCL4{slash}PMA3{slash}RG8-Pad6)") (class "Default")
      (node (ref "U1") (pin "6") (pinfunction "AN12/C2IND/RPG8/SCL4/PMA3/RG8_6") (pintype "bidirectional"))
    )
    (net (code "176") (name "unconnected-(U1-AN13{slash}C1INC{slash}RPG7{slash}SDA4{slash}PMA4{slash}RG7-Pad5)") (class "Default")
      (node (ref "U1") (pin "5") (pinfunction "AN13/C1INC/RPG7/SDA4/PMA4/RG7_5") (pintype "bidirectional"))
    )
    (net (code "177") (name "unconnected-(U1-AN14{slash}C1IND{slash}RPG6{slash}SCK2{slash}PMA5{slash}RG6-Pad4)") (class "Default")
      (node (ref "U1") (pin "4") (pinfunction "AN14/C1IND/RPG6/SCK2/PMA5/RG6_4") (pintype "bidirectional"))
    )
    (net (code "178") (name "unconnected-(U1-AN15{slash}ETXD1{slash}PMD7{slash}RE7-Pad3)") (class "Default")
      (node (ref "U1") (pin "3") (pinfunction "AN15/ETXD1/PMD7/RE7_3") (pintype "bidirectional"))
    )
    (net (code "179") (name "unconnected-(U1-AN16{slash}ETXD0{slash}PMD6{slash}RE6-Pad2)") (class "Default")
      (node (ref "U1") (pin "2") (pinfunction "AN16/ETXD0/PMD6/RE6_2") (pintype "bidirectional"))
    )
    (net (code "180") (name "unconnected-(U1-AN17{slash}ETXEN{slash}RPE5{slash}PMD5{slash}RE5-Pad1)") (class "Default")
      (node (ref "U1") (pin "1") (pinfunction "AN17/ETXEN/RPE5/PMD5/RE5_1") (pintype "bidirectional"))
    )
    (net (code "181") (name "unconnected-(U1-AN18{slash}ERXERR{slash}PMD4{slash}RE4-Pad64)") (class "Default")
      (node (ref "U1") (pin "64") (pinfunction "AN18/ERXERR/PMD4/RE4_64") (pintype "bidirectional"))
    )
    (net (code "182") (name "unconnected-(U1-AN45{slash}C1INA{slash}RPB5{slash}RB5-Pad11)") (class "Default")
      (node (ref "U1") (pin "11") (pinfunction "AN45/C1INA/RPB5/RB5_11") (pintype "bidirectional"))
    )
    (net (code "183") (name "unconnected-(U1-AN48{slash}RPB8{slash}PMA10{slash}RB8-Pad21)") (class "Default")
      (node (ref "U1") (pin "21") (pinfunction "AN48/RPB8/PMA10/RB8_21") (pintype "bidirectional"))
    )
    (net (code "184") (name "unconnected-(U1-AN49{slash}RPB9{slash}PMA7{slash}RB9-Pad22)") (class "Default")
      (node (ref "U1") (pin "22") (pinfunction "AN49/RPB9/PMA7/RB9_22") (pintype "bidirectional"))
    )
    (net (code "185") (name "unconnected-(U1-D+-Pad37)") (class "Default")
      (node (ref "U1") (pin "37") (pinfunction "D+_37") (pintype "bidirectional"))
    )
    (net (code "186") (name "unconnected-(U1-D--Pad36)") (class "Default")
      (node (ref "U1") (pin "36") (pinfunction "D-_36") (pintype "bidirectional"))
    )
    (net (code "187") (name "unconnected-(U1-ERXD3{slash}AETXD1{slash}RPF0{slash}RF0-Pad56)") (class "Default")
      (node (ref "U1") (pin "56") (pinfunction "ERXD3/AETXD1/RPF0/RF0_56") (pintype "bidirectional"))
    )
    (net (code "188") (name "unconnected-(U1-OSC1{slash}CLKI{slash}RC12-Pad31)") (class "Default")
      (node (ref "U1") (pin "31") (pinfunction "OSC1/CLKI/RC12_31") (pintype "bidirectional"))
    )
    (net (code "189") (name "unconnected-(U1-OSC2{slash}CLKO{slash}RC15-Pad32)") (class "Default")
      (node (ref "U1") (pin "32") (pinfunction "OSC2/CLKO/RC15_32") (pintype "bidirectional"))
    )
    (net (code "190") (name "unconnected-(U1-PGEC2{slash}AN46{slash}RPB6{slash}RB6-Pad17)") (class "Default")
      (node (ref "U1") (pin "17") (pinfunction "PGEC2/AN46/RPB6/RB6_17") (pintype "bidirectional"))
    )
    (net (code "191") (name "unconnected-(U1-PGED2{slash}AN47{slash}RPB7{slash}RB7-Pad18)") (class "Default")
      (node (ref "U1") (pin "18") (pinfunction "PGED2/AN47/RPB7/RB7_18") (pintype "bidirectional"))
    )
    (net (code "192") (name "unconnected-(U1-RPF3{slash}USBID{slash}RF3-Pad38)") (class "Default")
      (node (ref "U1") (pin "38") (pinfunction "RPF3/USBID/RF3_38") (pintype "bidirectional"))
    )
    (net (code "193") (name "unconnected-(U1-RPF4{slash}SDA5{slash}PMA9{slash}RF4-Pad41)") (class "Default")
      (node (ref "U1") (pin "41") (pinfunction "RPF4/SDA5/PMA9/RF4_41") (pintype "bidirectional"))
    )
    (net (code "194") (name "unconnected-(U1-RPF5{slash}SCL5{slash}PMA8{slash}RF5-Pad42)") (class "Default")
      (node (ref "U1") (pin "42") (pinfunction "RPF5/SCL5/PMA8/RF5_42") (pintype "bidirectional"))
    )
    (net (code "195") (name "unconnected-(U1-SOSCI{slash}RPC13{slash}RC13-Pad47)") (class "Default")
      (node (ref "U1") (pin "47") (pinfunction "SOSCI/RPC13/RC13_47") (pintype "bidirectional"))
    )
    (net (code "196") (name "unconnected-(U1-SOSCO{slash}RPC14{slash}T1CK{slash}RC14-Pad48)") (class "Default")
      (node (ref "U1") (pin "48") (pinfunction "SOSCO/RPC14/T1CK/RC14_48") (pintype "bidirectional"))
    )
    (net (code "197") (name "unconnected-(U1-SQICS0{slash}RPD4{slash}PMWR{slash}RD4-Pad52)") (class "Default")
      (node (ref "U1") (pin "52") (pinfunction "SQICS0/RPD4/PMWR/RD4_52") (pintype "bidirectional"))
    )
    (net (code "198") (name "unconnected-(U1-SQICS1{slash}RPD5{slash}PMRD{slash}RD5-Pad53)") (class "Default")
      (node (ref "U1") (pin "53") (pinfunction "SQICS1/RPD5/PMRD/RD5_53") (pintype "bidirectional"))
    )
    (net (code "199") (name "unconnected-(U1-TCK{slash}AN7{slash}PMA11{slash}RB12-Pad27)") (class "Default")
      (node (ref "U1") (pin "27") (pinfunction "TCK/AN7/PMA11/RB12_27") (pintype "bidirectional"))
    )
    (net (code "200") (name "unconnected-(U1-TDI{slash}AN8{slash}RB13-Pad28)") (class "Default")
      (node (ref "U1") (pin "28") (pinfunction "TDI/AN8/RB13_28") (pintype "bidirectional"))
    )
    (net (code "201") (name "unconnected-(U1-TDO{slash}AN6{slash}PMA12{slash}RB11-Pad24)") (class "Default")
      (node (ref "U1") (pin "24") (pinfunction "TDO/AN6/PMA12/RB11_24") (pintype "bidirectional"))
    )
    (net (code "202") (name "unconnected-(U1-TMS{slash}CVREFOUT{slash}AN5{slash}RPB10{slash}PMA13{slash}RB10-Pad23)") (class "Default")
      (node (ref "U1") (pin "23") (pinfunction "TMS/CVREFOUT/AN5/RPB10/PMA13/RB10_23") (pintype "bidirectional"))
    )
    (net (code "203") (name "unconnected-(U1-TRCLK{slash}SQICLK{slash}ERXD2{slash}AETXD0{slash}RPF1{slash}RF1-Pad57)") (class "Default")
      (node (ref "U1") (pin "57") (pinfunction "TRCLK/SQICLK/ERXD2/AETXD0/RPF1/RF1_57") (pintype "bidirectional"))
    )
    (net (code "204") (name "unconnected-(U1-TRD0{slash}SQID0{slash}ERXD1{slash}PMD0{slash}RE0-Pad58)") (class "Default")
      (node (ref "U1") (pin "58") (pinfunction "TRD0/SQID0/ERXD1/PMD0/RE0_58") (pintype "bidirectional"))
    )
    (net (code "205") (name "unconnected-(U1-TRD1{slash}SQID1{slash}ERXD0{slash}PMD1{slash}RE1-Pad61)") (class "Default")
      (node (ref "U1") (pin "61") (pinfunction "TRD1/SQID1/ERXD0/PMD1/RE1_61") (pintype "bidirectional"))
    )
    (net (code "206") (name "unconnected-(U1-TRD2{slash}SQID2{slash}ERXDV{slash}ECRSDV{slash}AECRSDV{slash}PMD2{slash}RE2-Pad62)") (class "Default")
      (node (ref "U1") (pin "62") (pinfunction "TRD2/SQID2/ERXDV/ECRSDV/AECRSDV/PMD2/RE2_62") (pintype "bidirectional"))
    )
    (net (code "207") (name "unconnected-(U1-TRD3{slash}SQID3{slash}ERXCLK{slash}EREFCLK{slash}RPE3{slash}PMD3{slash}RE3-Pad63)") (class "Default")
      (node (ref "U1") (pin "63") (pinfunction "TRD3/SQID3/ERXCLK/EREFCLK/RPE3/PMD3/RE3_63") (pintype "bidirectional"))
    )
  )
)
